# main.net
KiCad netlist of a schematic drawn in EAGLE
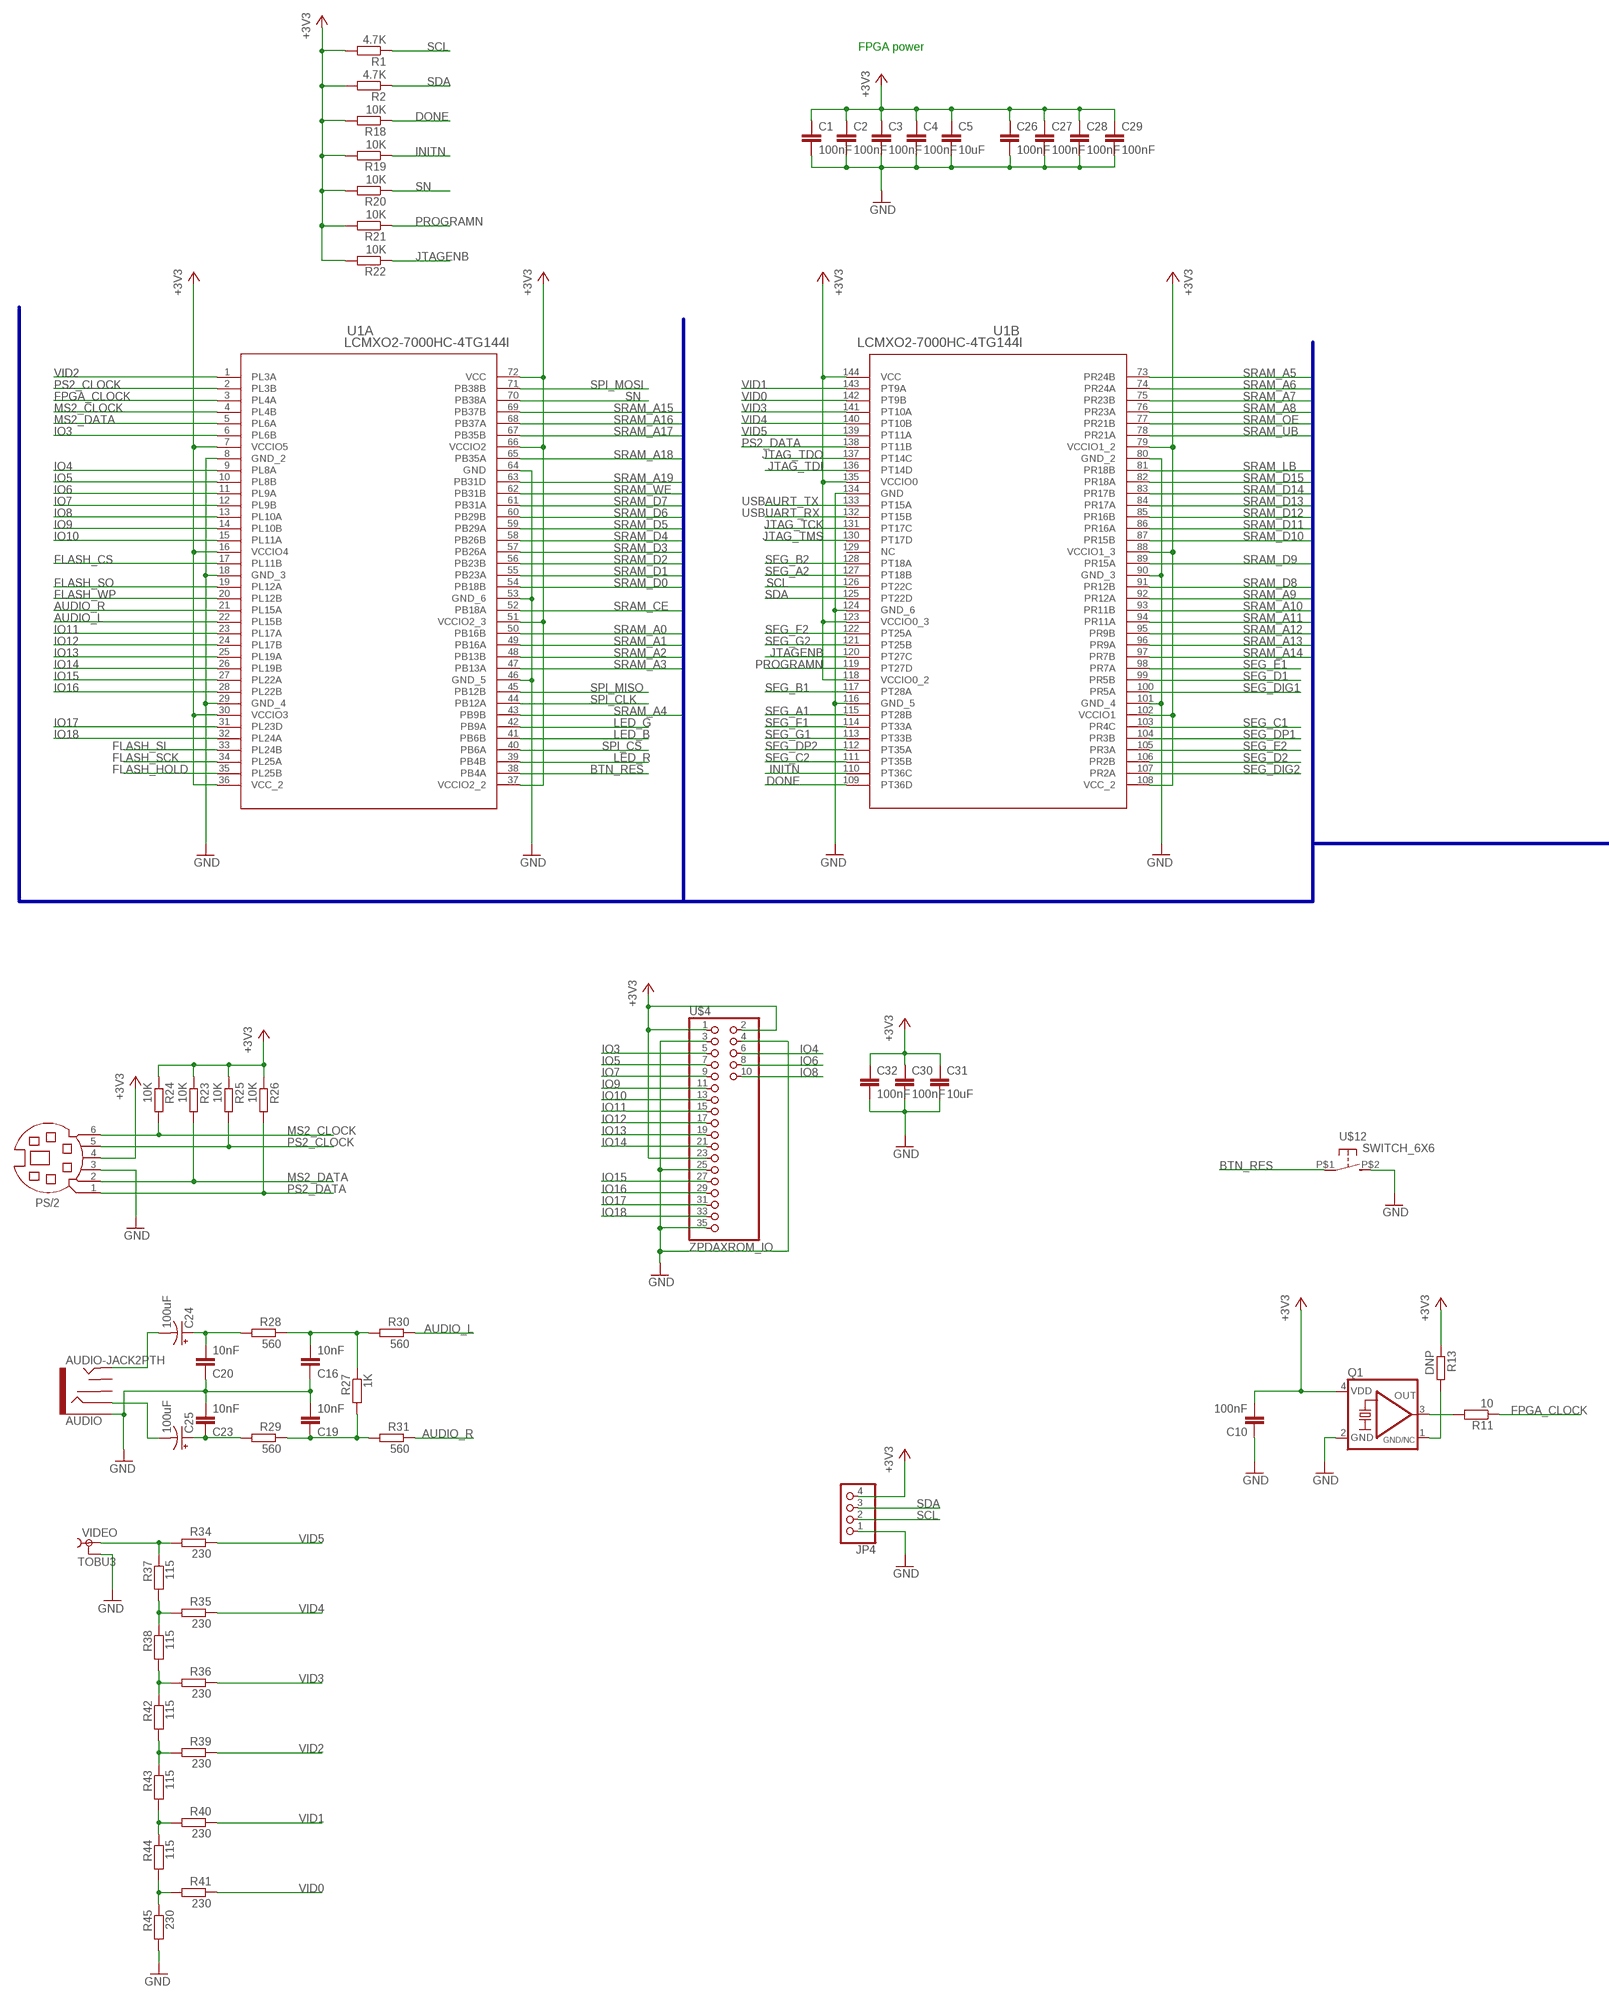
[diagram p0: schematic, sheet 1, part 1 of 2]
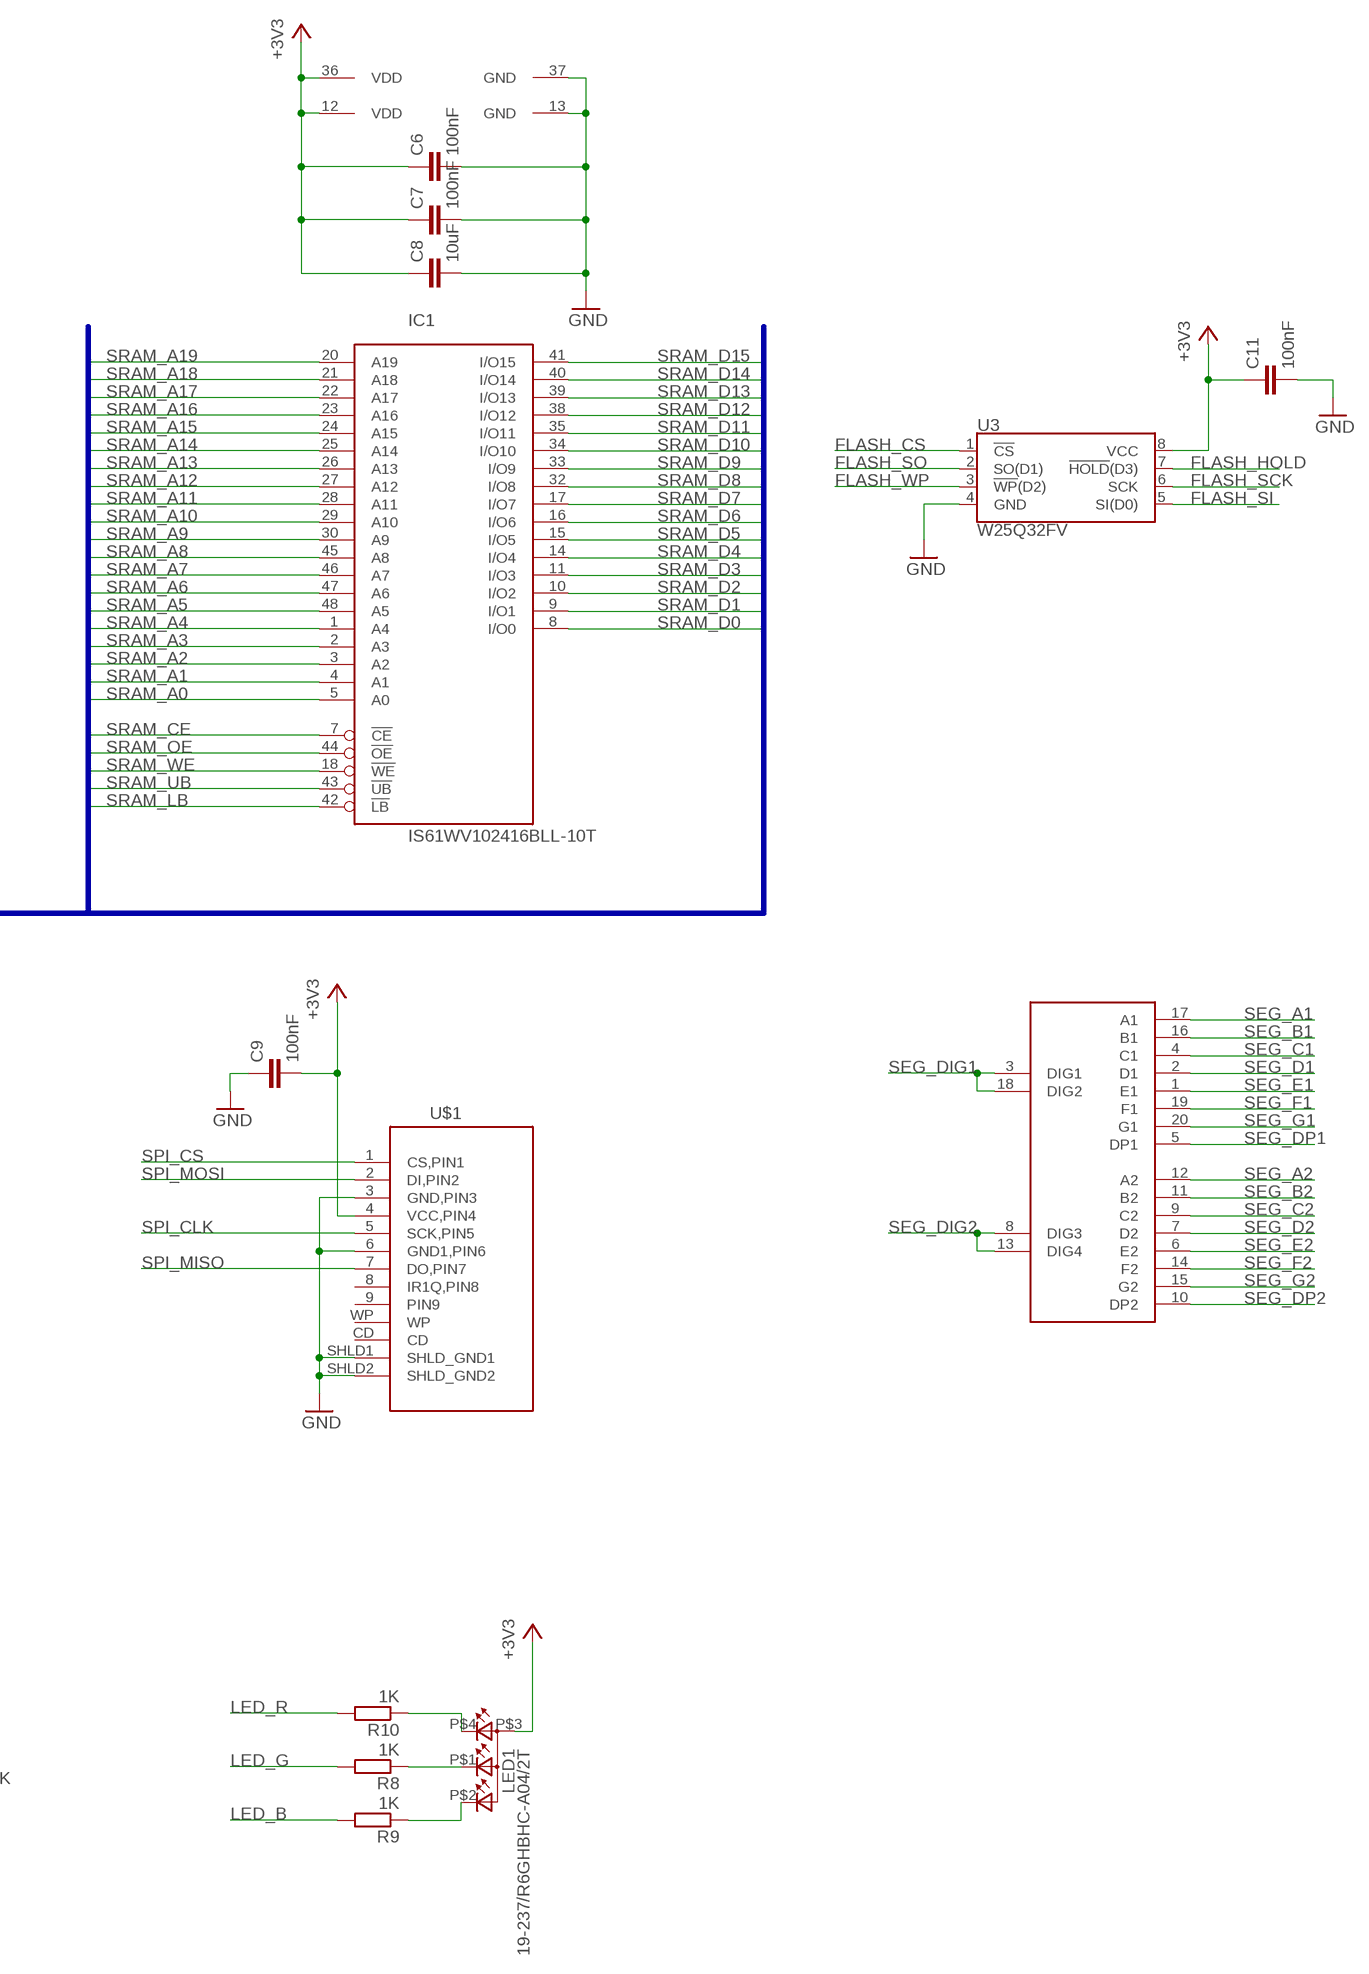
[diagram p1: schematic, sheet 1, part 2 of 2]
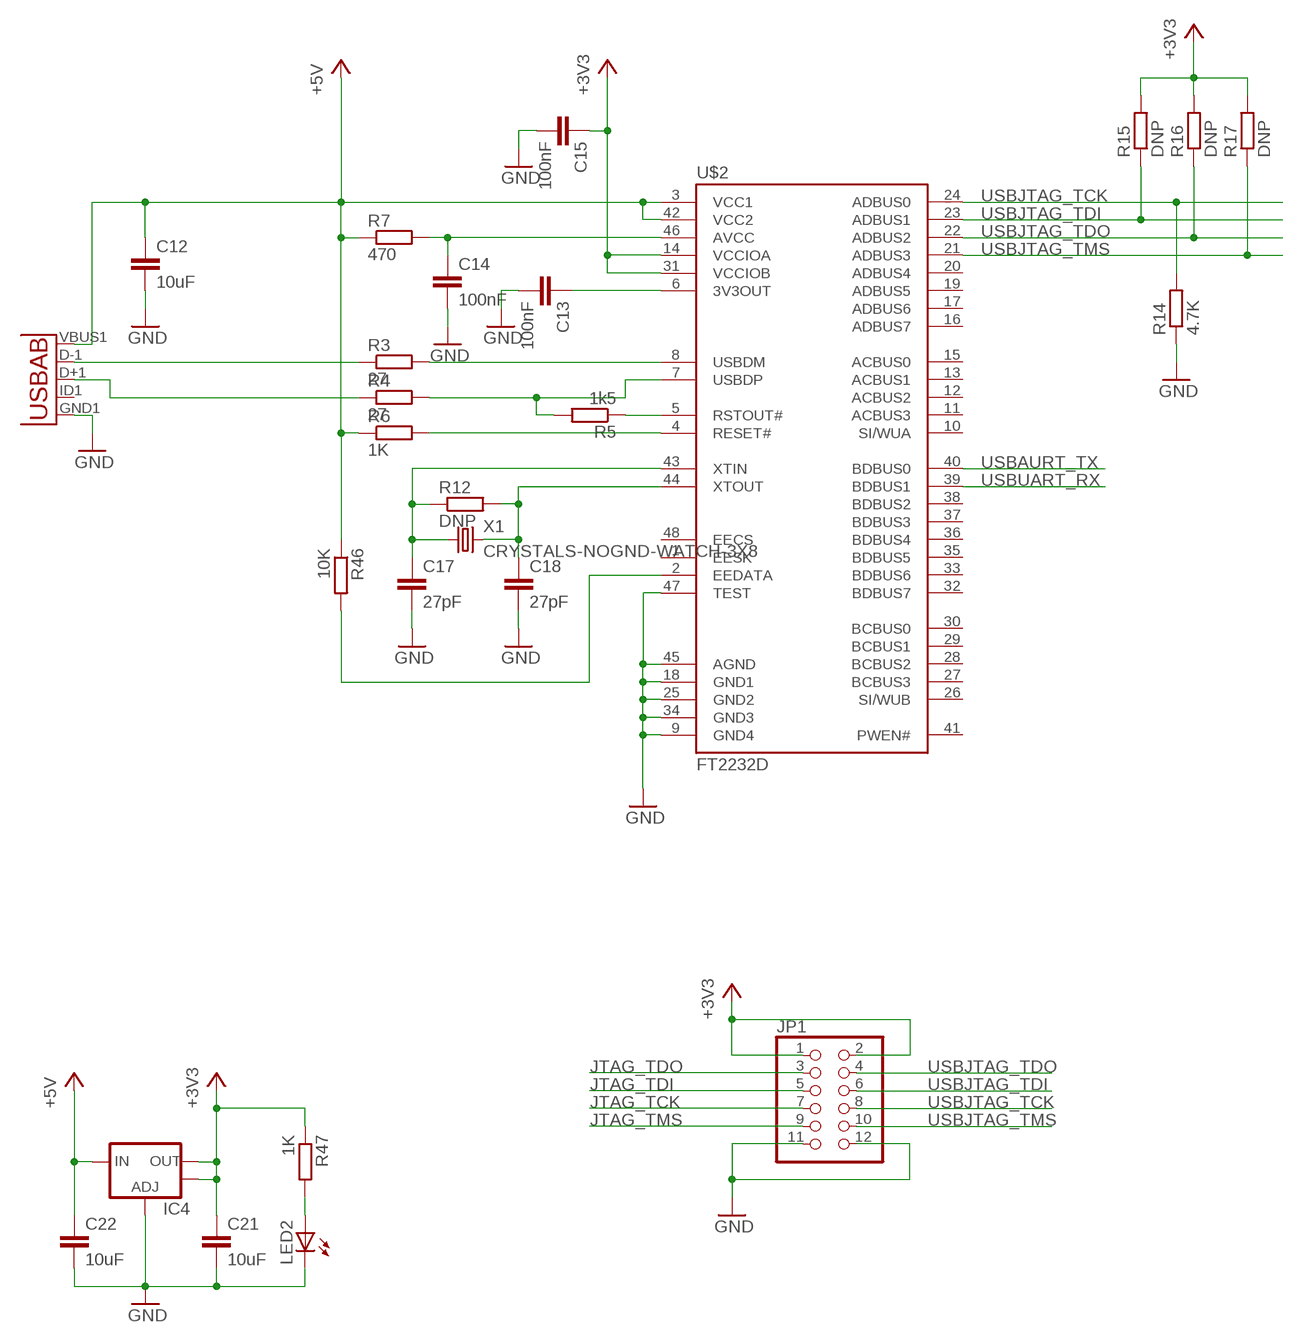
[diagram p2: schematic, sheet 2]

(export (version "E")
  (design (tool "Eeschema 10.0.6"))
  (components
    (comp (ref "AUDIO")
      (value "AUDIO-JACK2PTH")
      (footprint "eagle-import:AUDIO-JACK")
      (libsource (lib "eagle-import") (part "AUDIO-JACK2PTH"))
    )
    (comp (ref "C1")
      (value "100nF")
      (footprint "eagle-import:C0603")
      (libsource (lib "eagle-import") (part "C-EUC0603"))
    )
    (comp (ref "C2")
      (value "100nF")
      (footprint "eagle-import:C0603")
      (libsource (lib "eagle-import") (part "C-EUC0603"))
    )
    (comp (ref "C3")
      (value "100nF")
      (footprint "eagle-import:C0603")
      (libsource (lib "eagle-import") (part "C-EUC0603"))
    )
    (comp (ref "C4")
      (value "100nF")
      (footprint "eagle-import:C0603")
      (libsource (lib "eagle-import") (part "C-EUC0603"))
    )
    (comp (ref "C5")
      (value "10uF")
      (footprint "eagle-import:C0805")
      (libsource (lib "eagle-import") (part "C-EUC0805"))
    )
    (comp (ref "C6")
      (value "100nF")
      (footprint "eagle-import:C0603")
      (libsource (lib "eagle-import") (part "C-EUC0603"))
    )
    (comp (ref "C7")
      (value "100nF")
      (footprint "eagle-import:C0603")
      (libsource (lib "eagle-import") (part "C-EUC0603"))
    )
    (comp (ref "C8")
      (value "10uF")
      (footprint "eagle-import:C0805")
      (libsource (lib "eagle-import") (part "C-EUC0805"))
    )
    (comp (ref "C9")
      (value "100nF")
      (footprint "eagle-import:C0603")
      (libsource (lib "eagle-import") (part "C-EUC0603"))
    )
    (comp (ref "C10")
      (value "100nF")
      (footprint "eagle-import:C0603")
      (libsource (lib "eagle-import") (part "C-EUC0603"))
    )
    (comp (ref "C11")
      (value "100nF")
      (footprint "eagle-import:C0603")
      (libsource (lib "eagle-import") (part "C-EUC0603"))
    )
    (comp (ref "C16")
      (value "10nF")
      (footprint "eagle-import:C0603")
      (libsource (lib "eagle-import") (part "C-EUC0603"))
    )
    (comp (ref "C19")
      (value "10nF")
      (footprint "eagle-import:C0603")
      (libsource (lib "eagle-import") (part "C-EUC0603"))
    )
    (comp (ref "C20")
      (value "10nF")
      (footprint "eagle-import:C0603")
      (libsource (lib "eagle-import") (part "C-EUC0603"))
    )
    (comp (ref "C23")
      (value "10nF")
      (footprint "eagle-import:C0603")
      (libsource (lib "eagle-import") (part "C-EUC0603"))
    )
    (comp (ref "C24")
      (value "100uF")
      (footprint "eagle-import:EIA7343")
      (libsource (lib "eagle-import") (part "CAP_POL7343"))
    )
    (comp (ref "C25")
      (value "100uF")
      (footprint "eagle-import:EIA7343")
      (libsource (lib "eagle-import") (part "CAP_POL7343"))
    )
    (comp (ref "C26")
      (value "100nF")
      (footprint "eagle-import:C0603")
      (libsource (lib "eagle-import") (part "C-EUC0603"))
    )
    (comp (ref "C27")
      (value "100nF")
      (footprint "eagle-import:C0603")
      (libsource (lib "eagle-import") (part "C-EUC0603"))
    )
    (comp (ref "C28")
      (value "100nF")
      (footprint "eagle-import:C0603")
      (libsource (lib "eagle-import") (part "C-EUC0603"))
    )
    (comp (ref "C29")
      (value "100nF")
      (footprint "eagle-import:C0603")
      (libsource (lib "eagle-import") (part "C-EUC0603"))
    )
    (comp (ref "C30")
      (value "100nF")
      (footprint "eagle-import:C0603")
      (libsource (lib "eagle-import") (part "C-EUC0603"))
    )
    (comp (ref "C31")
      (value "10uF")
      (footprint "eagle-import:C0805")
      (libsource (lib "eagle-import") (part "C-EUC0805"))
    )
    (comp (ref "C32")
      (value "100nF")
      (footprint "eagle-import:C0603")
      (libsource (lib "eagle-import") (part "C-EUC0603"))
    )
    (comp (ref "IC1")
      (value "IS61WV102416BLL-10T")
      (footprint "eagle-import:TSOP-I-48-12X40MM")
      (libsource (lib "eagle-import") (part "IS61WV102416BLL-T10"))
    )
    (comp (ref "JP4")
      (value "PINHD-1X4")
      (footprint "eagle-import:1X04")
      (libsource (lib "eagle-import") (part "PINHD-1X4"))
    )
    (comp (ref "LED1")
      (value "19-237/R6GHBHC-A04/2T")
      (footprint "eagle-import:19-237_R6GHBHC-A04_2T")
      (libsource (lib "eagle-import") (part "19-237/R6GHBHC-A04/2T"))
    )
    (comp (ref "PS/2")
      (value "MD06SS")
      (footprint "eagle-import:MDIN06SS")
      (libsource (lib "eagle-import") (part "MD06SS"))
    )
    (comp (ref "Q1")
      (value "KXO-TCXO-CMOS-82")
      (footprint "eagle-import:7.0X5.0_KXO-82-TCXO")
      (libsource (lib "eagle-import") (part "KXO-TCXO-CMOS-82"))
    )
    (comp (ref "R1")
      (value "4.7K")
      (footprint "eagle-import:R0603")
      (libsource (lib "eagle-import") (part "R-EU_R0603"))
    )
    (comp (ref "R2")
      (value "4.7K")
      (footprint "eagle-import:R0603")
      (libsource (lib "eagle-import") (part "R-EU_R0603"))
    )
    (comp (ref "R8")
      (value "1K")
      (footprint "eagle-import:R0603")
      (libsource (lib "eagle-import") (part "R-EU_R0603"))
    )
    (comp (ref "R9")
      (value "1K")
      (footprint "eagle-import:R0603")
      (libsource (lib "eagle-import") (part "R-EU_R0603"))
    )
    (comp (ref "R10")
      (value "1K")
      (footprint "eagle-import:R0603")
      (libsource (lib "eagle-import") (part "R-EU_R0603"))
    )
    (comp (ref "R11")
      (value "10")
      (footprint "eagle-import:R0603")
      (libsource (lib "eagle-import") (part "R-EU_R0603"))
    )
    (comp (ref "R13")
      (value "DNP")
      (footprint "eagle-import:R0603")
      (libsource (lib "eagle-import") (part "R-EU_R0603"))
    )
    (comp (ref "R18")
      (value "10K")
      (footprint "eagle-import:R0603")
      (libsource (lib "eagle-import") (part "R-EU_R0603"))
    )
    (comp (ref "R19")
      (value "10K")
      (footprint "eagle-import:R0603")
      (libsource (lib "eagle-import") (part "R-EU_R0603"))
    )
    (comp (ref "R20")
      (value "10K")
      (footprint "eagle-import:R0603")
      (libsource (lib "eagle-import") (part "R-EU_R0603"))
    )
    (comp (ref "R21")
      (value "10K")
      (footprint "eagle-import:R0603")
      (libsource (lib "eagle-import") (part "R-EU_R0603"))
    )
    (comp (ref "R22")
      (value "10K")
      (footprint "eagle-import:R0603")
      (libsource (lib "eagle-import") (part "R-EU_R0603"))
    )
    (comp (ref "R23")
      (value "10K")
      (footprint "eagle-import:R0603")
      (libsource (lib "eagle-import") (part "R-EU_R0603"))
    )
    (comp (ref "R24")
      (value "10K")
      (footprint "eagle-import:R0603")
      (libsource (lib "eagle-import") (part "R-EU_R0603"))
    )
    (comp (ref "R25")
      (value "10K")
      (footprint "eagle-import:R0603")
      (libsource (lib "eagle-import") (part "R-EU_R0603"))
    )
    (comp (ref "R26")
      (value "10K")
      (footprint "eagle-import:R0603")
      (libsource (lib "eagle-import") (part "R-EU_R0603"))
    )
    (comp (ref "R27")
      (value "1K")
      (footprint "eagle-import:R0603")
      (libsource (lib "eagle-import") (part "R-EU_R0603"))
    )
    (comp (ref "R28")
      (value "560")
      (footprint "eagle-import:R0603")
      (libsource (lib "eagle-import") (part "R-EU_R0603"))
    )
    (comp (ref "R29")
      (value "560")
      (footprint "eagle-import:R0603")
      (libsource (lib "eagle-import") (part "R-EU_R0603"))
    )
    (comp (ref "R30")
      (value "560")
      (footprint "eagle-import:R0603")
      (libsource (lib "eagle-import") (part "R-EU_R0603"))
    )
    (comp (ref "R31")
      (value "560")
      (footprint "eagle-import:R0603")
      (libsource (lib "eagle-import") (part "R-EU_R0603"))
    )
    (comp (ref "R34")
      (value "230")
      (footprint "eagle-import:R0603")
      (libsource (lib "eagle-import") (part "R-EU_R0603"))
    )
    (comp (ref "R35")
      (value "230")
      (footprint "eagle-import:R0603")
      (libsource (lib "eagle-import") (part "R-EU_R0603"))
    )
    (comp (ref "R36")
      (value "230")
      (footprint "eagle-import:R0603")
      (libsource (lib "eagle-import") (part "R-EU_R0603"))
    )
    (comp (ref "R37")
      (value "115")
      (footprint "eagle-import:R0603")
      (libsource (lib "eagle-import") (part "R-EU_R0603"))
    )
    (comp (ref "R38")
      (value "115")
      (footprint "eagle-import:R0603")
      (libsource (lib "eagle-import") (part "R-EU_R0603"))
    )
    (comp (ref "R39")
      (value "230")
      (footprint "eagle-import:R0603")
      (libsource (lib "eagle-import") (part "R-EU_R0603"))
    )
    (comp (ref "R40")
      (value "230")
      (footprint "eagle-import:R0603")
      (libsource (lib "eagle-import") (part "R-EU_R0603"))
    )
    (comp (ref "R41")
      (value "230")
      (footprint "eagle-import:R0603")
      (libsource (lib "eagle-import") (part "R-EU_R0603"))
    )
    (comp (ref "R42")
      (value "115")
      (footprint "eagle-import:R0603")
      (libsource (lib "eagle-import") (part "R-EU_R0603"))
    )
    (comp (ref "R43")
      (value "115")
      (footprint "eagle-import:R0603")
      (libsource (lib "eagle-import") (part "R-EU_R0603"))
    )
    (comp (ref "R44")
      (value "115")
      (footprint "eagle-import:R0603")
      (libsource (lib "eagle-import") (part "R-EU_R0603"))
    )
    (comp (ref "R45")
      (value "230")
      (footprint "eagle-import:R0603")
      (libsource (lib "eagle-import") (part "R-EU_R0603"))
    )
    (comp (ref "U$1")
      (value "FCI_SD_SOCKET")
      (footprint "eagle-import:SD-MMC_SOCKET-PP")
      (fields (field (name "MF") "FCI") (field (name "MPN") "10067847-001RLF"))
      (libsource (lib "eagle-import") (part "FCI_SD_SOCKET"))
    )
    (comp (ref "U$3")
      (value "GS2020CR-G")
      (footprint "eagle-import:GS2020CR")
      (libsource (lib "eagle-import") (part "GS2020CR-G"))
    )
    (comp (ref "U$4")
      (value "ZPDAXROM_IO")
      (footprint "eagle-import:2X18_ZPDAXROM_IO")
      (libsource (lib "eagle-import") (part "ZPDAXROM_IO"))
    )
    (comp (ref "U$12")
      (value "SWITCH_6X6")
      (footprint "eagle-import:SWITCH_6X6")
      (libsource (lib "eagle-import") (part "SWITCH_6X6"))
    )
    (comp (ref "U1")
      (value "LCMXO2-7000HC-4TG144I")
      (footprint "eagle-import:TQFP144")
      (fields (field (name "MANUFACTURER_PART_NUMBER") "LCMXO27000HC4TG144I"))
      (libsource (lib "eagle-import") (part "LCMXO2-7000HC-4TG144I"))
    )
    (comp (ref "U3")
      (value "W25Q32FV")
      (footprint "eagle-import:SOIC-8")
      (libsource (lib "eagle-import") (part "W25Q32FVSS"))
    )
    (comp (ref "VIDEO")
      (value "TOBU3")
      (footprint "eagle-import:TOBU3")
      (fields (field (name "MF") "FARNELL") (field (name "MPN") "TOBU 3"))
      (libsource (lib "eagle-import") (part "TOBU3"))
    )
    (comp (ref "C12")
      (value "10uF")
      (footprint "eagle-import:C0805")
      (libsource (lib "eagle-import") (part "C-EUC0805"))
    )
    (comp (ref "C13")
      (value "100nF")
      (footprint "eagle-import:C0603")
      (libsource (lib "eagle-import") (part "C-EUC0603"))
    )
    (comp (ref "C14")
      (value "100nF")
      (footprint "eagle-import:C0603")
      (libsource (lib "eagle-import") (part "C-EUC0603"))
    )
    (comp (ref "C15")
      (value "100nF")
      (footprint "eagle-import:C0603")
      (libsource (lib "eagle-import") (part "C-EUC0603"))
    )
    (comp (ref "C17")
      (value "27pF")
      (footprint "eagle-import:C0603")
      (libsource (lib "eagle-import") (part "C-EUC0603"))
    )
    (comp (ref "C18")
      (value "27pF")
      (footprint "eagle-import:C0603")
      (libsource (lib "eagle-import") (part "C-EUC0603"))
    )
    (comp (ref "C21")
      (value "10uF")
      (footprint "eagle-import:C0805")
      (libsource (lib "eagle-import") (part "C-EUC0805"))
    )
    (comp (ref "C22")
      (value "10uF")
      (footprint "eagle-import:C0805")
      (libsource (lib "eagle-import") (part "C-EUC0805"))
    )
    (comp (ref "IC4")
      (value "V_REG_LM1117SOT223")
      (footprint "eagle-import:SOT223")
      (libsource (lib "eagle-import") (part "V_REG_LM1117SOT223"))
    )
    (comp (ref "JP1")
      (value "PINHD-2X6")
      (footprint "eagle-import:2X06")
      (libsource (lib "eagle-import") (part "PINHD-2X6"))
    )
    (comp (ref "LED2")
      (value "LEDCHIPLED_0603")
      (footprint "eagle-import:CHIPLED_0603")
      (libsource (lib "eagle-import") (part "LEDCHIPLED_0603"))
    )
    (comp (ref "R3")
      (value "27")
      (footprint "eagle-import:R0603")
      (libsource (lib "eagle-import") (part "R-EU_R0603"))
    )
    (comp (ref "R4")
      (value "27")
      (footprint "eagle-import:R0603")
      (libsource (lib "eagle-import") (part "R-EU_R0603"))
    )
    (comp (ref "R5")
      (value "1k5")
      (footprint "eagle-import:R0603")
      (libsource (lib "eagle-import") (part "R-EU_R0603"))
    )
    (comp (ref "R6")
      (value "1K")
      (footprint "eagle-import:R0603")
      (libsource (lib "eagle-import") (part "R-EU_R0603"))
    )
    (comp (ref "R7")
      (value "470")
      (footprint "eagle-import:R0603")
      (libsource (lib "eagle-import") (part "R-EU_R0603"))
    )
    (comp (ref "R12")
      (value "DNP")
      (footprint "eagle-import:R0603")
      (libsource (lib "eagle-import") (part "R-EU_R0603"))
    )
    (comp (ref "R14")
      (value "4.7K")
      (footprint "eagle-import:R0603")
      (libsource (lib "eagle-import") (part "R-EU_R0603"))
    )
    (comp (ref "R15")
      (value "DNP")
      (footprint "eagle-import:R0603")
      (libsource (lib "eagle-import") (part "R-EU_R0603"))
    )
    (comp (ref "R16")
      (value "DNP")
      (footprint "eagle-import:R0603")
      (libsource (lib "eagle-import") (part "R-EU_R0603"))
    )
    (comp (ref "R17")
      (value "DNP")
      (footprint "eagle-import:R0603")
      (libsource (lib "eagle-import") (part "R-EU_R0603"))
    )
    (comp (ref "R46")
      (value "10K")
      (footprint "eagle-import:R0603")
      (libsource (lib "eagle-import") (part "R-EU_R0603"))
    )
    (comp (ref "R47")
      (value "1K")
      (footprint "eagle-import:R0603")
      (libsource (lib "eagle-import") (part "R-EU_R0603"))
    )
    (comp (ref "U$2")
      (value "FT2232D")
      (footprint "eagle-import:LQFP-48")
      (libsource (lib "eagle-import") (part "FT2232D"))
    )
    (comp (ref "U2")
      (value "USB\"\"")
      (footprint "eagle-import:USB-MICRO-SMD")
      (libsource (lib "eagle-import") (part "USB{dblquote}{dblquote}"))
    )
    (comp (ref "X1")
      (value "CRYSTALS-NOGND-WATCH-3X8")
      (footprint "eagle-import:WATCH-3X8")
      (libsource (lib "eagle-import") (part "CRYSTALS-NOGND-WATCH-3X8"))
    )
  )
  (nets
    (net (code "1") (name "+3V3") (class "Default")
      (node (ref "C1") (pin "1") (pinfunction "1_1") (pintype "passive"))
      (node (ref "C10") (pin "2") (pinfunction "2_2") (pintype "passive"))
      (node (ref "C11") (pin "1") (pinfunction "1_1") (pintype "passive"))
      (node (ref "C15") (pin "1") (pinfunction "1_1") (pintype "passive"))
      (node (ref "C2") (pin "1") (pinfunction "1_1") (pintype "passive"))
      (node (ref "C21") (pin "1") (pinfunction "1_1") (pintype "passive"))
      (node (ref "C26") (pin "1") (pinfunction "1_1") (pintype "passive"))
      (node (ref "C27") (pin "1") (pinfunction "1_1") (pintype "passive"))
      (node (ref "C28") (pin "1") (pinfunction "1_1") (pintype "passive"))
      (node (ref "C29") (pin "1") (pinfunction "1_1") (pintype "passive"))
      (node (ref "C3") (pin "1") (pinfunction "1_1") (pintype "passive"))
      (node (ref "C30") (pin "1") (pinfunction "1_1") (pintype "passive"))
      (node (ref "C31") (pin "1") (pinfunction "1_1") (pintype "passive"))
      (node (ref "C32") (pin "1") (pinfunction "1_1") (pintype "passive"))
      (node (ref "C4") (pin "1") (pinfunction "1_1") (pintype "passive"))
      (node (ref "C5") (pin "1") (pinfunction "1_1") (pintype "passive"))
      (node (ref "C6") (pin "1") (pinfunction "1_1") (pintype "passive"))
      (node (ref "C7") (pin "1") (pinfunction "1_1") (pintype "passive"))
      (node (ref "C8") (pin "1") (pinfunction "1_1") (pintype "passive"))
      (node (ref "C9") (pin "2") (pinfunction "2_2") (pintype "passive"))
      (node (ref "IC1") (pin "12") (pinfunction "VDD_12") (pintype "power_in"))
      (node (ref "IC1") (pin "36") (pinfunction "VDD_36") (pintype "power_in"))
      (node (ref "IC4") (pin "2") (pinfunction "OUT_2") (pintype "output"))
      (node (ref "IC4") (pin "4") (pinfunction "OUT_4") (pintype "output"))
      (node (ref "JP1") (pin "1") (pinfunction "1_1") (pintype "passive"))
      (node (ref "JP1") (pin "2") (pinfunction "2_2") (pintype "passive"))
      (node (ref "JP4") (pin "4") (pinfunction "4_4") (pintype "passive"))
      (node (ref "LED1") (pin "P$3") (pinfunction "A_P$3") (pintype "passive"))
      (node (ref "PS/2") (pin "4") (pinfunction "4_4") (pintype "passive"))
      (node (ref "Q1") (pin "4") (pinfunction "VDD_4") (pintype "power_in"))
      (node (ref "R1") (pin "2") (pinfunction "2_2") (pintype "passive"))
      (node (ref "R13") (pin "1") (pinfunction "1_1") (pintype "passive"))
      (node (ref "R15") (pin "2") (pinfunction "2_2") (pintype "passive"))
      (node (ref "R16") (pin "2") (pinfunction "2_2") (pintype "passive"))
      (node (ref "R17") (pin "2") (pinfunction "2_2") (pintype "passive"))
      (node (ref "R18") (pin "2") (pinfunction "2_2") (pintype "passive"))
      (node (ref "R19") (pin "2") (pinfunction "2_2") (pintype "passive"))
      (node (ref "R2") (pin "2") (pinfunction "2_2") (pintype "passive"))
      (node (ref "R20") (pin "2") (pinfunction "2_2") (pintype "passive"))
      (node (ref "R21") (pin "2") (pinfunction "2_2") (pintype "passive"))
      (node (ref "R22") (pin "2") (pinfunction "2_2") (pintype "passive"))
      (node (ref "R23") (pin "1") (pinfunction "1_1") (pintype "passive"))
      (node (ref "R24") (pin "1") (pinfunction "1_1") (pintype "passive"))
      (node (ref "R25") (pin "1") (pinfunction "1_1") (pintype "passive"))
      (node (ref "R26") (pin "1") (pinfunction "1_1") (pintype "passive"))
      (node (ref "R47") (pin "1") (pinfunction "1_1") (pintype "passive"))
      (node (ref "U$1") (pin "4") (pinfunction "VCC,PIN4_4") (pintype "bidirectional"))
      (node (ref "U$2") (pin "14") (pinfunction "VCCIOA_14") (pintype "power_in"))
      (node (ref "U$2") (pin "31") (pinfunction "VCCIOB_31") (pintype "bidirectional"))
      (node (ref "U$4") (pin "1") (pinfunction "1_1") (pintype "passive"))
      (node (ref "U$4") (pin "2") (pinfunction "2_2") (pintype "passive"))
      (node (ref "U$4") (pin "23") (pinfunction "23_23") (pintype "passive"))
      (node (ref "U1") (pin "102") (pinfunction "VCCIO1_102") (pintype "power_in"))
      (node (ref "U1") (pin "108") (pinfunction "VCC_2_108") (pintype "power_in"))
      (node (ref "U1") (pin "118") (pinfunction "VCCIO0_2_118") (pintype "power_in"))
      (node (ref "U1") (pin "123") (pinfunction "VCCIO0_3_123") (pintype "power_in"))
      (node (ref "U1") (pin "135") (pinfunction "VCCIO0_135") (pintype "power_in"))
      (node (ref "U1") (pin "144") (pinfunction "VCC_144") (pintype "power_in"))
      (node (ref "U1") (pin "16") (pinfunction "VCCIO4_16") (pintype "power_in"))
      (node (ref "U1") (pin "30") (pinfunction "VCCIO3_30") (pintype "power_in"))
      (node (ref "U1") (pin "36") (pinfunction "VCC_2_36") (pintype "power_in"))
      (node (ref "U1") (pin "37") (pinfunction "VCCIO2_2_37") (pintype "power_in"))
      (node (ref "U1") (pin "51") (pinfunction "VCCIO2_3_51") (pintype "power_in"))
      (node (ref "U1") (pin "66") (pinfunction "VCCIO2_66") (pintype "power_in"))
      (node (ref "U1") (pin "7") (pinfunction "VCCIO5_7") (pintype "power_in"))
      (node (ref "U1") (pin "72") (pinfunction "VCC_72") (pintype "power_in"))
      (node (ref "U1") (pin "79") (pinfunction "VCCIO1_2_79") (pintype "power_in"))
      (node (ref "U1") (pin "88") (pinfunction "VCCIO1_3_88") (pintype "power_in"))
      (node (ref "U3") (pin "8") (pinfunction "VCC_8") (pintype "bidirectional"))
    )
    (net (code "2") (name "+5V") (class "Default")
      (node (ref "C12") (pin "1") (pinfunction "1_1") (pintype "passive"))
      (node (ref "C22") (pin "1") (pinfunction "1_1") (pintype "passive"))
      (node (ref "IC4") (pin "3") (pinfunction "IN_3") (pintype "input"))
      (node (ref "R46") (pin "1") (pinfunction "1_1") (pintype "passive"))
      (node (ref "R6") (pin "1") (pinfunction "1_1") (pintype "passive"))
      (node (ref "R7") (pin "1") (pinfunction "1_1") (pintype "passive"))
      (node (ref "U$2") (pin "3") (pinfunction "VCC1_3") (pintype "power_in"))
      (node (ref "U$2") (pin "42") (pinfunction "VCC2_42") (pintype "power_in"))
      (node (ref "U2") (pin "VBUS1") (pinfunction "VBUS_VBUS1") (pintype "bidirectional"))
    )
    (net (code "3") (name "AUDIO_L") (class "Default")
      (node (ref "R30") (pin "1") (pinfunction "1_1") (pintype "passive"))
      (node (ref "U1") (pin "22") (pinfunction "PL15B_22") (pintype "passive"))
    )
    (net (code "4") (name "AUDIO_R") (class "Default")
      (node (ref "R31") (pin "1") (pinfunction "1_1") (pintype "passive"))
      (node (ref "U1") (pin "21") (pinfunction "PL15A_21") (pintype "passive"))
    )
    (net (code "5") (name "BTN_RES") (class "Default")
      (node (ref "U$12") (pin "P$1") (pinfunction "P_P$1") (pintype "passive"))
      (node (ref "U1") (pin "38") (pinfunction "PB4A_38") (pintype "passive"))
    )
    (net (code "6") (name "DONE") (class "Default")
      (node (ref "R18") (pin "1") (pinfunction "1_1") (pintype "passive"))
      (node (ref "U1") (pin "109") (pinfunction "PT36D_109") (pintype "passive"))
    )
    (net (code "7") (name "FLASH_CS") (class "Default")
      (node (ref "U1") (pin "17") (pinfunction "PL11B_17") (pintype "passive"))
      (node (ref "U3") (pin "1") (pinfunction "~{CS}_1") (pintype "bidirectional"))
    )
    (net (code "8") (name "FLASH_HOLD") (class "Default")
      (node (ref "U1") (pin "35") (pinfunction "PL25B_35") (pintype "passive"))
      (node (ref "U3") (pin "7") (pinfunction "~{HOLD}(D3)_7") (pintype "bidirectional"))
    )
    (net (code "9") (name "FLASH_SCK") (class "Default")
      (node (ref "U1") (pin "34") (pinfunction "PL25A_34") (pintype "passive"))
      (node (ref "U3") (pin "6") (pinfunction "SCK_6") (pintype "bidirectional"))
    )
    (net (code "10") (name "FLASH_SI") (class "Default")
      (node (ref "U1") (pin "33") (pinfunction "PL24B_33") (pintype "passive"))
      (node (ref "U3") (pin "5") (pinfunction "SI(D0)_5") (pintype "bidirectional"))
    )
    (net (code "11") (name "FLASH_SO") (class "Default")
      (node (ref "U1") (pin "19") (pinfunction "PL12A_19") (pintype "passive"))
      (node (ref "U3") (pin "2") (pinfunction "SO(D1)_2") (pintype "bidirectional"))
    )
    (net (code "12") (name "FLASH_WP") (class "Default")
      (node (ref "U1") (pin "20") (pinfunction "PL12B_20") (pintype "passive"))
      (node (ref "U3") (pin "3") (pinfunction "~{WP}(D2)_3") (pintype "bidirectional"))
    )
    (net (code "13") (name "FPGA_CLOCK") (class "Default")
      (node (ref "R11") (pin "1") (pinfunction "1_1") (pintype "passive"))
      (node (ref "U1") (pin "3") (pinfunction "PL4A_3") (pintype "passive"))
    )
    (net (code "14") (name "GND") (class "Default")
      (node (ref "AUDIO") (pin "SLEEVE") (pinfunction "SLEEVE_SLEEVE") (pintype "bidirectional"))
      (node (ref "C1") (pin "2") (pinfunction "2_2") (pintype "passive"))
      (node (ref "C10") (pin "1") (pinfunction "1_1") (pintype "passive"))
      (node (ref "C11") (pin "2") (pinfunction "2_2") (pintype "passive"))
      (node (ref "C12") (pin "2") (pinfunction "2_2") (pintype "passive"))
      (node (ref "C13") (pin "2") (pinfunction "2_2") (pintype "passive"))
      (node (ref "C14") (pin "2") (pinfunction "2_2") (pintype "passive"))
      (node (ref "C15") (pin "2") (pinfunction "2_2") (pintype "passive"))
      (node (ref "C16") (pin "1") (pinfunction "1_1") (pintype "passive"))
      (node (ref "C17") (pin "2") (pinfunction "2_2") (pintype "passive"))
      (node (ref "C18") (pin "2") (pinfunction "2_2") (pintype "passive"))
      (node (ref "C19") (pin "2") (pinfunction "2_2") (pintype "passive"))
      (node (ref "C2") (pin "2") (pinfunction "2_2") (pintype "passive"))
      (node (ref "C20") (pin "1") (pinfunction "1_1") (pintype "passive"))
      (node (ref "C21") (pin "2") (pinfunction "2_2") (pintype "passive"))
      (node (ref "C22") (pin "2") (pinfunction "2_2") (pintype "passive"))
      (node (ref "C23") (pin "2") (pinfunction "2_2") (pintype "passive"))
      (node (ref "C26") (pin "2") (pinfunction "2_2") (pintype "passive"))
      (node (ref "C27") (pin "2") (pinfunction "2_2") (pintype "passive"))
      (node (ref "C28") (pin "2") (pinfunction "2_2") (pintype "passive"))
      (node (ref "C29") (pin "2") (pinfunction "2_2") (pintype "passive"))
      (node (ref "C3") (pin "2") (pinfunction "2_2") (pintype "passive"))
      (node (ref "C30") (pin "2") (pinfunction "2_2") (pintype "passive"))
      (node (ref "C31") (pin "2") (pinfunction "2_2") (pintype "passive"))
      (node (ref "C32") (pin "2") (pinfunction "2_2") (pintype "passive"))
      (node (ref "C4") (pin "2") (pinfunction "2_2") (pintype "passive"))
      (node (ref "C5") (pin "2") (pinfunction "2_2") (pintype "passive"))
      (node (ref "C6") (pin "2") (pinfunction "2_2") (pintype "passive"))
      (node (ref "C7") (pin "2") (pinfunction "2_2") (pintype "passive"))
      (node (ref "C8") (pin "2") (pinfunction "2_2") (pintype "passive"))
      (node (ref "C9") (pin "1") (pinfunction "1_1") (pintype "passive"))
      (node (ref "IC1") (pin "13") (pinfunction "GND_13") (pintype "power_in"))
      (node (ref "IC1") (pin "37") (pinfunction "GND_37") (pintype "power_in"))
      (node (ref "IC4") (pin "1") (pinfunction "ADJ_1") (pintype "input"))
      (node (ref "JP1") (pin "11") (pinfunction "11_11") (pintype "passive"))
      (node (ref "JP1") (pin "12") (pinfunction "12_12") (pintype "passive"))
      (node (ref "JP4") (pin "1") (pinfunction "1_1") (pintype "passive"))
      (node (ref "LED2") (pin "C") (pinfunction "C_C") (pintype "passive"))
      (node (ref "PS/2") (pin "3") (pinfunction "3_3") (pintype "passive"))
      (node (ref "Q1") (pin "2") (pinfunction "GND_2") (pintype "power_in"))
      (node (ref "R14") (pin "1") (pinfunction "1_1") (pintype "passive"))
      (node (ref "R45") (pin "2") (pinfunction "2_2") (pintype "passive"))
      (node (ref "U$1") (pin "3") (pinfunction "GND,PIN3_3") (pintype "bidirectional"))
      (node (ref "U$1") (pin "6") (pinfunction "GND1,PIN6_6") (pintype "bidirectional"))
      (node (ref "U$1") (pin "SHLD1") (pinfunction "SHLD_GND1_SHLD1") (pintype "bidirectional"))
      (node (ref "U$1") (pin "SHLD2") (pinfunction "SHLD_GND2_SHLD2") (pintype "bidirectional"))
      (node (ref "U$12") (pin "P$2") (pinfunction "S_P$2") (pintype "passive"))
      (node (ref "U$2") (pin "18") (pinfunction "GND1_18") (pintype "power_in"))
      (node (ref "U$2") (pin "25") (pinfunction "GND2_25") (pintype "power_in"))
      (node (ref "U$2") (pin "34") (pinfunction "GND3_34") (pintype "power_in"))
      (node (ref "U$2") (pin "45") (pinfunction "AGND_45") (pintype "power_in"))
      (node (ref "U$2") (pin "47") (pinfunction "TEST_47") (pintype "input"))
      (node (ref "U$2") (pin "9") (pinfunction "GND4_9") (pintype "bidirectional"))
      (node (ref "U$4") (pin "25") (pinfunction "25_25") (pintype "passive"))
      (node (ref "U$4") (pin "3") (pinfunction "3_3") (pintype "passive"))
      (node (ref "U$4") (pin "35") (pinfunction "35_35") (pintype "passive"))
      (node (ref "U$4") (pin "4") (pinfunction "4_4") (pintype "passive"))
      (node (ref "U1") (pin "101") (pinfunction "GND_4_101") (pintype "power_in"))
      (node (ref "U1") (pin "116") (pinfunction "GND_5_116") (pintype "power_in"))
      (node (ref "U1") (pin "124") (pinfunction "GND_6_124") (pintype "power_in"))
      (node (ref "U1") (pin "134") (pinfunction "GND_134") (pintype "power_in"))
      (node (ref "U1") (pin "18") (pinfunction "GND_3_18") (pintype "power_in"))
      (node (ref "U1") (pin "29") (pinfunction "GND_4_29") (pintype "power_in"))
      (node (ref "U1") (pin "46") (pinfunction "GND_5_46") (pintype "power_in"))
      (node (ref "U1") (pin "53") (pinfunction "GND_6_53") (pintype "power_in"))
      (node (ref "U1") (pin "64") (pinfunction "GND_64") (pintype "power_in"))
      (node (ref "U1") (pin "8") (pinfunction "GND_2_8") (pintype "power_in"))
      (node (ref "U1") (pin "80") (pinfunction "GND_2_80") (pintype "power_in"))
      (node (ref "U1") (pin "90") (pinfunction "GND_3_90") (pintype "power_in"))
      (node (ref "U2") (pin "GND1") (pinfunction "GND_GND1") (pintype "bidirectional"))
      (node (ref "U3") (pin "4") (pinfunction "GND_4") (pintype "bidirectional"))
      (node (ref "VIDEO") (pin "2") (pinfunction "2_2") (pintype "passive"))
      (node (ref "VIDEO") (pin "2@1") (pinfunction "2_2@1") (pintype "passive"))
      (node (ref "VIDEO") (pin "2@2") (pinfunction "2_2@2") (pintype "passive"))
    )
    (net (code "15") (name "INITN") (class "Default")
      (node (ref "R19") (pin "1") (pinfunction "1_1") (pintype "passive"))
      (node (ref "U1") (pin "110") (pinfunction "PT36C_110") (pintype "passive"))
    )
    (net (code "16") (name "IO3") (class "Default")
      (node (ref "U$4") (pin "5") (pinfunction "5_5") (pintype "passive"))
      (node (ref "U1") (pin "6") (pinfunction "PL6B_6") (pintype "passive"))
    )
    (net (code "17") (name "IO4") (class "Default")
      (node (ref "U$4") (pin "6") (pinfunction "6_6") (pintype "passive"))
      (node (ref "U1") (pin "9") (pinfunction "PL8A_9") (pintype "passive"))
    )
    (net (code "18") (name "IO5") (class "Default")
      (node (ref "U$4") (pin "7") (pinfunction "7_7") (pintype "passive"))
      (node (ref "U1") (pin "10") (pinfunction "PL8B_10") (pintype "passive"))
    )
    (net (code "19") (name "IO6") (class "Default")
      (node (ref "U$4") (pin "8") (pinfunction "8_8") (pintype "passive"))
      (node (ref "U1") (pin "11") (pinfunction "PL9A_11") (pintype "passive"))
    )
    (net (code "20") (name "IO7") (class "Default")
      (node (ref "U$4") (pin "9") (pinfunction "9_9") (pintype "passive"))
      (node (ref "U1") (pin "12") (pinfunction "PL9B_12") (pintype "passive"))
    )
    (net (code "21") (name "IO8") (class "Default")
      (node (ref "U$4") (pin "10") (pinfunction "10_10") (pintype "passive"))
      (node (ref "U1") (pin "13") (pinfunction "PL10A_13") (pintype "passive"))
    )
    (net (code "22") (name "IO9") (class "Default")
      (node (ref "U$4") (pin "11") (pinfunction "11_11") (pintype "passive"))
      (node (ref "U1") (pin "14") (pinfunction "PL10B_14") (pintype "passive"))
    )
    (net (code "23") (name "IO10") (class "Default")
      (node (ref "U$4") (pin "13") (pinfunction "13_13") (pintype "passive"))
      (node (ref "U1") (pin "15") (pinfunction "PL11A_15") (pintype "passive"))
    )
    (net (code "24") (name "IO11") (class "Default")
      (node (ref "U$4") (pin "15") (pinfunction "15_15") (pintype "passive"))
      (node (ref "U1") (pin "23") (pinfunction "PL17A_23") (pintype "passive"))
    )
    (net (code "25") (name "IO12") (class "Default")
      (node (ref "U$4") (pin "17") (pinfunction "17_17") (pintype "passive"))
      (node (ref "U1") (pin "24") (pinfunction "PL17B_24") (pintype "passive"))
    )
    (net (code "26") (name "IO13") (class "Default")
      (node (ref "U$4") (pin "19") (pinfunction "19_19") (pintype "passive"))
      (node (ref "U1") (pin "25") (pinfunction "PL19A_25") (pintype "passive"))
    )
    (net (code "27") (name "IO14") (class "Default")
      (node (ref "U$4") (pin "21") (pinfunction "21_21") (pintype "passive"))
      (node (ref "U1") (pin "26") (pinfunction "PL19B_26") (pintype "passive"))
    )
    (net (code "28") (name "IO15") (class "Default")
      (node (ref "U$4") (pin "27") (pinfunction "27_27") (pintype "passive"))
      (node (ref "U1") (pin "27") (pinfunction "PL22A_27") (pintype "passive"))
    )
    (net (code "29") (name "IO16") (class "Default")
      (node (ref "U$4") (pin "29") (pinfunction "29_29") (pintype "passive"))
      (node (ref "U1") (pin "28") (pinfunction "PL22B_28") (pintype "passive"))
    )
    (net (code "30") (name "IO17") (class "Default")
      (node (ref "U$4") (pin "31") (pinfunction "31_31") (pintype "passive"))
      (node (ref "U1") (pin "31") (pinfunction "PL23D_31") (pintype "passive"))
    )
    (net (code "31") (name "IO18") (class "Default")
      (node (ref "U$4") (pin "33") (pinfunction "33_33") (pintype "passive"))
      (node (ref "U1") (pin "32") (pinfunction "PL24A_32") (pintype "passive"))
    )
    (net (code "32") (name "JTAGENB") (class "Default")
      (node (ref "R22") (pin "1") (pinfunction "1_1") (pintype "passive"))
      (node (ref "U1") (pin "120") (pinfunction "PT27C_120") (pintype "passive"))
    )
    (net (code "33") (name "JTAG_TCK") (class "Default")
      (node (ref "JP1") (pin "7") (pinfunction "7_7") (pintype "passive"))
      (node (ref "U1") (pin "131") (pinfunction "PT17C_131") (pintype "passive"))
    )
    (net (code "34") (name "JTAG_TDI") (class "Default")
      (node (ref "JP1") (pin "5") (pinfunction "5_5") (pintype "passive"))
      (node (ref "U1") (pin "136") (pinfunction "PT14D_136") (pintype "passive"))
    )
    (net (code "35") (name "JTAG_TDO") (class "Default")
      (node (ref "JP1") (pin "3") (pinfunction "3_3") (pintype "passive"))
      (node (ref "U1") (pin "137") (pinfunction "PT14C_137") (pintype "passive"))
    )
    (net (code "36") (name "JTAG_TMS") (class "Default")
      (node (ref "JP1") (pin "9") (pinfunction "9_9") (pintype "passive"))
      (node (ref "U1") (pin "130") (pinfunction "PT17D_130") (pintype "passive"))
    )
    (net (code "37") (name "LED_B") (class "Default")
      (node (ref "R9") (pin "2") (pinfunction "2_2") (pintype "passive"))
      (node (ref "U1") (pin "41") (pinfunction "PB6B_41") (pintype "passive"))
    )
    (net (code "38") (name "LED_G") (class "Default")
      (node (ref "R8") (pin "2") (pinfunction "2_2") (pintype "passive"))
      (node (ref "U1") (pin "42") (pinfunction "PB9A_42") (pintype "passive"))
    )
    (net (code "39") (name "LED_R") (class "Default")
      (node (ref "R10") (pin "2") (pinfunction "2_2") (pintype "passive"))
      (node (ref "U1") (pin "39") (pinfunction "PB4B_39") (pintype "passive"))
    )
    (net (code "40") (name "MS2_CLOCK") (class "Default")
      (node (ref "PS/2") (pin "6") (pinfunction "6_6") (pintype "passive"))
      (node (ref "R24") (pin "2") (pinfunction "2_2") (pintype "passive"))
      (node (ref "U1") (pin "4") (pinfunction "PL4B_4") (pintype "passive"))
    )
    (net (code "41") (name "MS2_DATA") (class "Default")
      (node (ref "PS/2") (pin "2") (pinfunction "2_2") (pintype "passive"))
      (node (ref "R23") (pin "2") (pinfunction "2_2") (pintype "passive"))
      (node (ref "U1") (pin "5") (pinfunction "PL6A_5") (pintype "passive"))
    )
    (net (code "42") (name "Net-(C16-Pad2)") (class "Default")
      (node (ref "C16") (pin "2") (pinfunction "2_2") (pintype "passive"))
      (node (ref "R27") (pin "1") (pinfunction "1_1") (pintype "passive"))
      (node (ref "R28") (pin "1") (pinfunction "1_1") (pintype "passive"))
      (node (ref "R30") (pin "2") (pinfunction "2_2") (pintype "passive"))
    )
    (net (code "43") (name "Net-(C19-Pad1)") (class "Default")
      (node (ref "C19") (pin "1") (pinfunction "1_1") (pintype "passive"))
      (node (ref "R27") (pin "2") (pinfunction "2_2") (pintype "passive"))
      (node (ref "R29") (pin "1") (pinfunction "1_1") (pintype "passive"))
      (node (ref "R31") (pin "2") (pinfunction "2_2") (pintype "passive"))
    )
    (net (code "44") (name "Net-(C24-+)") (class "Default")
      (node (ref "C20") (pin "2") (pinfunction "2_2") (pintype "passive"))
      (node (ref "C24") (pin "A") (pinfunction "+_A") (pintype "passive"))
      (node (ref "R28") (pin "2") (pinfunction "2_2") (pintype "passive"))
    )
    (net (code "45") (name "Net-(C24--)") (class "Default")
      (node (ref "AUDIO") (pin "TIP") (pinfunction "TIP_TIP") (pintype "bidirectional"))
      (node (ref "C24") (pin "C") (pinfunction "-_C") (pintype "passive"))
    )
    (net (code "46") (name "Net-(C25-+)") (class "Default")
      (node (ref "C23") (pin "1") (pinfunction "1_1") (pintype "passive"))
      (node (ref "C25") (pin "A") (pinfunction "+_A") (pintype "passive"))
      (node (ref "R29") (pin "2") (pinfunction "2_2") (pintype "passive"))
    )
    (net (code "47") (name "Net-(C25--)") (class "Default")
      (node (ref "AUDIO") (pin "RING") (pinfunction "RING_RING") (pintype "bidirectional"))
      (node (ref "C25") (pin "C") (pinfunction "-_C") (pintype "passive"))
    )
    (net (code "48") (name "Net-(LED1-CBLUE)") (class "Default")
      (node (ref "LED1") (pin "P$1") (pinfunction "CBLUE_P$1") (pintype "passive"))
      (node (ref "R8") (pin "1") (pinfunction "1_1") (pintype "passive"))
    )
    (net (code "49") (name "Net-(LED1-CGREEN)") (class "Default")
      (node (ref "LED1") (pin "P$2") (pinfunction "CGREEN_P$2") (pintype "passive"))
      (node (ref "R9") (pin "1") (pinfunction "1_1") (pintype "passive"))
    )
    (net (code "50") (name "Net-(LED1-CRED)") (class "Default")
      (node (ref "LED1") (pin "P$4") (pinfunction "CRED_P$4") (pintype "passive"))
      (node (ref "R10") (pin "1") (pinfunction "1_1") (pintype "passive"))
    )
    (net (code "51") (name "Net-(LED2-PadA)") (class "Default")
      (node (ref "LED2") (pin "A") (pinfunction "A_A") (pintype "passive"))
      (node (ref "R47") (pin "2") (pinfunction "2_2") (pintype "passive"))
    )
    (net (code "52") (name "Net-(Q1-GND{slash}NC)") (class "Default")
      (node (ref "Q1") (pin "1") (pinfunction "GND/NC_1") (pintype "power_in"))
      (node (ref "R13") (pin "2") (pinfunction "2_2") (pintype "passive"))
    )
    (net (code "53") (name "Net-(Q1-OUT)") (class "Default")
      (node (ref "Q1") (pin "3") (pinfunction "OUT_3") (pintype "output"))
      (node (ref "R11") (pin "2") (pinfunction "2_2") (pintype "passive"))
    )
    (net (code "54") (name "Net-(R34-Pad2)") (class "Default")
      (node (ref "R34") (pin "2") (pinfunction "2_2") (pintype "passive"))
      (node (ref "R37") (pin "1") (pinfunction "1_1") (pintype "passive"))
      (node (ref "VIDEO") (pin "1") (pinfunction "1_1") (pintype "passive"))
    )
    (net (code "55") (name "Net-(R35-Pad2)") (class "Default")
      (node (ref "R35") (pin "2") (pinfunction "2_2") (pintype "passive"))
      (node (ref "R37") (pin "2") (pinfunction "2_2") (pintype "passive"))
      (node (ref "R38") (pin "1") (pinfunction "1_1") (pintype "passive"))
    )
    (net (code "56") (name "Net-(R36-Pad2)") (class "Default")
      (node (ref "R36") (pin "2") (pinfunction "2_2") (pintype "passive"))
      (node (ref "R38") (pin "2") (pinfunction "2_2") (pintype "passive"))
      (node (ref "R42") (pin "1") (pinfunction "1_1") (pintype "passive"))
    )
    (net (code "57") (name "Net-(R39-Pad2)") (class "Default")
      (node (ref "R39") (pin "2") (pinfunction "2_2") (pintype "passive"))
      (node (ref "R42") (pin "2") (pinfunction "2_2") (pintype "passive"))
      (node (ref "R43") (pin "1") (pinfunction "1_1") (pintype "passive"))
    )
    (net (code "58") (name "Net-(R40-Pad2)") (class "Default")
      (node (ref "R40") (pin "2") (pinfunction "2_2") (pintype "passive"))
      (node (ref "R43") (pin "2") (pinfunction "2_2") (pintype "passive"))
      (node (ref "R44") (pin "1") (pinfunction "1_1") (pintype "passive"))
    )
    (net (code "59") (name "Net-(R41-Pad2)") (class "Default")
      (node (ref "R41") (pin "2") (pinfunction "2_2") (pintype "passive"))
      (node (ref "R44") (pin "2") (pinfunction "2_2") (pintype "passive"))
      (node (ref "R45") (pin "1") (pinfunction "1_1") (pintype "passive"))
    )
    (net (code "60") (name "Net-(U$2-3V3OUT)") (class "Default")
      (node (ref "C13") (pin "1") (pinfunction "1_1") (pintype "passive"))
      (node (ref "U$2") (pin "6") (pinfunction "3V3OUT_6") (pintype "output"))
    )
    (net (code "61") (name "Net-(U$2-AVCC)") (class "Default")
      (node (ref "C14") (pin "1") (pinfunction "1_1") (pintype "passive"))
      (node (ref "R7") (pin "2") (pinfunction "2_2") (pintype "passive"))
      (node (ref "U$2") (pin "46") (pinfunction "AVCC_46") (pintype "bidirectional"))
    )
    (net (code "62") (name "Net-(U$2-EEDATA)") (class "Default")
      (node (ref "R46") (pin "2") (pinfunction "2_2") (pintype "passive"))
      (node (ref "U$2") (pin "2") (pinfunction "EEDATA_2") (pintype "bidirectional"))
    )
    (net (code "63") (name "Net-(U$2-RESET#)") (class "Default")
      (node (ref "R6") (pin "2") (pinfunction "2_2") (pintype "passive"))
      (node (ref "U$2") (pin "4") (pinfunction "RESET#_4") (pintype "bidirectional"))
    )
    (net (code "64") (name "Net-(U$2-RSTOUT#)") (class "Default")
      (node (ref "R5") (pin "1") (pinfunction "1_1") (pintype "passive"))
      (node (ref "U$2") (pin "5") (pinfunction "RSTOUT#_5") (pintype "bidirectional"))
    )
    (net (code "65") (name "Net-(U$2-USBDM)") (class "Default")
      (node (ref "R3") (pin "2") (pinfunction "2_2") (pintype "passive"))
      (node (ref "U$2") (pin "8") (pinfunction "USBDM_8") (pintype "bidirectional"))
    )
    (net (code "66") (name "Net-(U$2-USBDP)") (class "Default")
      (node (ref "R4") (pin "2") (pinfunction "2_2") (pintype "passive"))
      (node (ref "R5") (pin "2") (pinfunction "2_2") (pintype "passive"))
      (node (ref "U$2") (pin "7") (pinfunction "USBDP_7") (pintype "bidirectional"))
    )
    (net (code "67") (name "Net-(U$2-XTIN)") (class "Default")
      (node (ref "C17") (pin "1") (pinfunction "1_1") (pintype "passive"))
      (node (ref "R12") (pin "1") (pinfunction "1_1") (pintype "passive"))
      (node (ref "U$2") (pin "43") (pinfunction "XTIN_43") (pintype "bidirectional"))
      (node (ref "X1") (pin "1") (pinfunction "1_1") (pintype "passive"))
    )
    (net (code "68") (name "Net-(U$2-XTOUT)") (class "Default")
      (node (ref "C18") (pin "1") (pinfunction "1_1") (pintype "passive"))
      (node (ref "R12") (pin "2") (pinfunction "2_2") (pintype "passive"))
      (node (ref "U$2") (pin "44") (pinfunction "XTOUT_44") (pintype "bidirectional"))
      (node (ref "X1") (pin "2") (pinfunction "2_2") (pintype "passive"))
    )
    (net (code "69") (name "Net-(U2-D+)") (class "Default")
      (node (ref "R4") (pin "1") (pinfunction "1_1") (pintype "passive"))
      (node (ref "U2") (pin "D+1") (pinfunction "D+_D+1") (pintype "bidirectional"))
    )
    (net (code "70") (name "Net-(U2-D-)") (class "Default")
      (node (ref "R3") (pin "1") (pinfunction "1_1") (pintype "passive"))
      (node (ref "U2") (pin "D-1") (pinfunction "D-_D-1") (pintype "bidirectional"))
    )
    (net (code "71") (name "PROGRAMN") (class "Default")
      (node (ref "R21") (pin "1") (pinfunction "1_1") (pintype "passive"))
      (node (ref "U1") (pin "119") (pinfunction "PT27D_119") (pintype "passive"))
    )
    (net (code "72") (name "PS2_CLOCK") (class "Default")
      (node (ref "PS/2") (pin "5") (pinfunction "5_5") (pintype "passive"))
      (node (ref "R25") (pin "2") (pinfunction "2_2") (pintype "passive"))
      (node (ref "U1") (pin "2") (pinfunction "PL3B_2") (pintype "passive"))
    )
    (net (code "73") (name "PS2_DATA") (class "Default")
      (node (ref "PS/2") (pin "1") (pinfunction "1_1") (pintype "passive"))
      (node (ref "R26") (pin "2") (pinfunction "2_2") (pintype "passive"))
      (node (ref "U1") (pin "138") (pinfunction "PT11B_138") (pintype "passive"))
    )
    (net (code "74") (name "SCL") (class "Default")
      (node (ref "JP4") (pin "2") (pinfunction "2_2") (pintype "passive"))
      (node (ref "R1") (pin "1") (pinfunction "1_1") (pintype "passive"))
      (node (ref "U1") (pin "126") (pinfunction "PT22C_126") (pintype "passive"))
    )
    (net (code "75") (name "SDA") (class "Default")
      (node (ref "JP4") (pin "3") (pinfunction "3_3") (pintype "passive"))
      (node (ref "R2") (pin "1") (pinfunction "1_1") (pintype "passive"))
      (node (ref "U1") (pin "125") (pinfunction "PT22D_125") (pintype "passive"))
    )
    (net (code "76") (name "SEG_A1") (class "Default")
      (node (ref "U$3") (pin "17") (pinfunction "A1_17") (pintype "bidirectional"))
      (node (ref "U1") (pin "115") (pinfunction "PT28B_115") (pintype "passive"))
    )
    (net (code "77") (name "SEG_A2") (class "Default")
      (node (ref "U$3") (pin "12") (pinfunction "A2_12") (pintype "bidirectional"))
      (node (ref "U1") (pin "127") (pinfunction "PT18B_127") (pintype "passive"))
    )
    (net (code "78") (name "SEG_B1") (class "Default")
      (node (ref "U$3") (pin "16") (pinfunction "B1_16") (pintype "bidirectional"))
      (node (ref "U1") (pin "117") (pinfunction "PT28A_117") (pintype "passive"))
    )
    (net (code "79") (name "SEG_B2") (class "Default")
      (node (ref "U$3") (pin "11") (pinfunction "B2_11") (pintype "bidirectional"))
      (node (ref "U1") (pin "128") (pinfunction "PT18A_128") (pintype "passive"))
    )
    (net (code "80") (name "SEG_C1") (class "Default")
      (node (ref "U$3") (pin "4") (pinfunction "C1_4") (pintype "bidirectional"))
      (node (ref "U1") (pin "103") (pinfunction "PR4C_103") (pintype "passive"))
    )
    (net (code "81") (name "SEG_C2") (class "Default")
      (node (ref "U$3") (pin "9") (pinfunction "C2_9") (pintype "bidirectional"))
      (node (ref "U1") (pin "111") (pinfunction "PT35B_111") (pintype "passive"))
    )
    (net (code "82") (name "SEG_D1") (class "Default")
      (node (ref "U$3") (pin "2") (pinfunction "D1_2") (pintype "bidirectional"))
      (node (ref "U1") (pin "99") (pinfunction "PR5B_99") (pintype "passive"))
    )
    (net (code "83") (name "SEG_D2") (class "Default")
      (node (ref "U$3") (pin "7") (pinfunction "D2_7") (pintype "bidirectional"))
      (node (ref "U1") (pin "106") (pinfunction "PR2B_106") (pintype "passive"))
    )
    (net (code "84") (name "SEG_DIG1") (class "Default")
      (node (ref "U$3") (pin "18") (pinfunction "DIG2_18") (pintype "bidirectional"))
      (node (ref "U$3") (pin "3") (pinfunction "DIG1_3") (pintype "bidirectional"))
      (node (ref "U1") (pin "100") (pinfunction "PR5A_100") (pintype "passive"))
    )
    (net (code "85") (name "SEG_DIG2") (class "Default")
      (node (ref "U$3") (pin "13") (pinfunction "DIG4_13") (pintype "bidirectional"))
      (node (ref "U$3") (pin "8") (pinfunction "DIG3_8") (pintype "bidirectional"))
      (node (ref "U1") (pin "107") (pinfunction "PR2A_107") (pintype "passive"))
    )
    (net (code "86") (name "SEG_DP1") (class "Default")
      (node (ref "U$3") (pin "5") (pinfunction "DP1_5") (pintype "bidirectional"))
      (node (ref "U1") (pin "104") (pinfunction "PR3B_104") (pintype "passive"))
    )
    (net (code "87") (name "SEG_DP2") (class "Default")
      (node (ref "U$3") (pin "10") (pinfunction "DP2_10") (pintype "bidirectional"))
      (node (ref "U1") (pin "112") (pinfunction "PT35A_112") (pintype "passive"))
    )
    (net (code "88") (name "SEG_E1") (class "Default")
      (node (ref "U$3") (pin "1") (pinfunction "E1_1") (pintype "bidirectional"))
      (node (ref "U1") (pin "98") (pinfunction "PR7A_98") (pintype "passive"))
    )
    (net (code "89") (name "SEG_E2") (class "Default")
      (node (ref "U$3") (pin "6") (pinfunction "E2_6") (pintype "bidirectional"))
      (node (ref "U1") (pin "105") (pinfunction "PR3A_105") (pintype "passive"))
    )
    (net (code "90") (name "SEG_F1") (class "Default")
      (node (ref "U$3") (pin "19") (pinfunction "F1_19") (pintype "bidirectional"))
      (node (ref "U1") (pin "114") (pinfunction "PT33A_114") (pintype "passive"))
    )
    (net (code "91") (name "SEG_F2") (class "Default")
      (node (ref "U$3") (pin "14") (pinfunction "F2_14") (pintype "bidirectional"))
      (node (ref "U1") (pin "122") (pinfunction "PT25A_122") (pintype "passive"))
    )
    (net (code "92") (name "SEG_G1") (class "Default")
      (node (ref "U$3") (pin "20") (pinfunction "G1_20") (pintype "bidirectional"))
      (node (ref "U1") (pin "113") (pinfunction "PT33B_113") (pintype "passive"))
    )
    (net (code "93") (name "SEG_G2") (class "Default")
      (node (ref "U$3") (pin "15") (pinfunction "G2_15") (pintype "bidirectional"))
      (node (ref "U1") (pin "121") (pinfunction "PT25B_121") (pintype "passive"))
    )
    (net (code "94") (name "SN") (class "Default")
      (node (ref "R20") (pin "1") (pinfunction "1_1") (pintype "passive"))
      (node (ref "U1") (pin "70") (pinfunction "PB38A_70") (pintype "passive"))
    )
    (net (code "95") (name "SPI_CLK") (class "Default")
      (node (ref "U$1") (pin "5") (pinfunction "SCK,PIN5_5") (pintype "bidirectional"))
      (node (ref "U1") (pin "44") (pinfunction "PB12A_44") (pintype "passive"))
    )
    (net (code "96") (name "SPI_CS") (class "Default")
      (node (ref "U$1") (pin "1") (pinfunction "CS,PIN1_1") (pintype "bidirectional"))
      (node (ref "U1") (pin "40") (pinfunction "PB6A_40") (pintype "passive"))
    )
    (net (code "97") (name "SPI_MISO") (class "Default")
      (node (ref "U$1") (pin "7") (pinfunction "DO,PIN7_7") (pintype "bidirectional"))
      (node (ref "U1") (pin "45") (pinfunction "PB12B_45") (pintype "passive"))
    )
    (net (code "98") (name "SPI_MOSI") (class "Default")
      (node (ref "U$1") (pin "2") (pinfunction "DI,PIN2_2") (pintype "bidirectional"))
      (node (ref "U1") (pin "71") (pinfunction "PB38B_71") (pintype "passive"))
    )
    (net (code "99") (name "SRAM_A0") (class "Default")
      (node (ref "IC1") (pin "5") (pinfunction "A0_5") (pintype "input"))
      (node (ref "U1") (pin "50") (pinfunction "PB16B_50") (pintype "passive"))
    )
    (net (code "100") (name "SRAM_A1") (class "Default")
      (node (ref "IC1") (pin "4") (pinfunction "A1_4") (pintype "input"))
      (node (ref "U1") (pin "49") (pinfunction "PB16A_49") (pintype "passive"))
    )
    (net (code "101") (name "SRAM_A2") (class "Default")
      (node (ref "IC1") (pin "3") (pinfunction "A2_3") (pintype "input"))
      (node (ref "U1") (pin "48") (pinfunction "PB13B_48") (pintype "passive"))
    )
    (net (code "102") (name "SRAM_A3") (class "Default")
      (node (ref "IC1") (pin "2") (pinfunction "A3_2") (pintype "input"))
      (node (ref "U1") (pin "47") (pinfunction "PB13A_47") (pintype "passive"))
    )
    (net (code "103") (name "SRAM_A4") (class "Default")
      (node (ref "IC1") (pin "1") (pinfunction "A4_1") (pintype "input"))
      (node (ref "U1") (pin "43") (pinfunction "PB9B_43") (pintype "passive"))
    )
    (net (code "104") (name "SRAM_A5") (class "Default")
      (node (ref "IC1") (pin "48") (pinfunction "A5_48") (pintype "input"))
      (node (ref "U1") (pin "73") (pinfunction "PR24B_73") (pintype "passive"))
    )
    (net (code "105") (name "SRAM_A6") (class "Default")
      (node (ref "IC1") (pin "47") (pinfunction "A6_47") (pintype "input"))
      (node (ref "U1") (pin "74") (pinfunction "PR24A_74") (pintype "passive"))
    )
    (net (code "106") (name "SRAM_A7") (class "Default")
      (node (ref "IC1") (pin "46") (pinfunction "A7_46") (pintype "input"))
      (node (ref "U1") (pin "75") (pinfunction "PR23B_75") (pintype "passive"))
    )
    (net (code "107") (name "SRAM_A8") (class "Default")
      (node (ref "IC1") (pin "45") (pinfunction "A8_45") (pintype "input"))
      (node (ref "U1") (pin "76") (pinfunction "PR23A_76") (pintype "passive"))
    )
    (net (code "108") (name "SRAM_A9") (class "Default")
      (node (ref "IC1") (pin "30") (pinfunction "A9_30") (pintype "input"))
      (node (ref "U1") (pin "92") (pinfunction "PR12A_92") (pintype "passive"))
    )
    (net (code "109") (name "SRAM_A10") (class "Default")
      (node (ref "IC1") (pin "29") (pinfunction "A10_29") (pintype "input"))
      (node (ref "U1") (pin "93") (pinfunction "PR11B_93") (pintype "passive"))
    )
    (net (code "110") (name "SRAM_A11") (class "Default")
      (node (ref "IC1") (pin "28") (pinfunction "A11_28") (pintype "input"))
      (node (ref "U1") (pin "94") (pinfunction "PR11A_94") (pintype "passive"))
    )
    (net (code "111") (name "SRAM_A12") (class "Default")
      (node (ref "IC1") (pin "27") (pinfunction "A12_27") (pintype "input"))
      (node (ref "U1") (pin "95") (pinfunction "PR9B_95") (pintype "passive"))
    )
    (net (code "112") (name "SRAM_A13") (class "Default")
      (node (ref "IC1") (pin "26") (pinfunction "A13_26") (pintype "input"))
      (node (ref "U1") (pin "96") (pinfunction "PR9A_96") (pintype "passive"))
    )
    (net (code "113") (name "SRAM_A14") (class "Default")
      (node (ref "IC1") (pin "25") (pinfunction "A14_25") (pintype "input"))
      (node (ref "U1") (pin "97") (pinfunction "PR7B_97") (pintype "passive"))
    )
    (net (code "114") (name "SRAM_A15") (class "Default")
      (node (ref "IC1") (pin "24") (pinfunction "A15_24") (pintype "input"))
      (node (ref "U1") (pin "69") (pinfunction "PB37B_69") (pintype "passive"))
    )
    (net (code "115") (name "SRAM_A16") (class "Default")
      (node (ref "IC1") (pin "23") (pinfunction "A16_23") (pintype "input"))
      (node (ref "U1") (pin "68") (pinfunction "PB37A_68") (pintype "passive"))
    )
    (net (code "116") (name "SRAM_A17") (class "Default")
      (node (ref "IC1") (pin "22") (pinfunction "A17_22") (pintype "input"))
      (node (ref "U1") (pin "67") (pinfunction "PB35B_67") (pintype "passive"))
    )
    (net (code "117") (name "SRAM_A18") (class "Default")
      (node (ref "IC1") (pin "21") (pinfunction "A18_21") (pintype "input"))
      (node (ref "U1") (pin "65") (pinfunction "PB35A_65") (pintype "passive"))
    )
    (net (code "118") (name "SRAM_A19") (class "Default")
      (node (ref "IC1") (pin "20") (pinfunction "A19_20") (pintype "input"))
      (node (ref "U1") (pin "63") (pinfunction "PB31D_63") (pintype "passive"))
    )
    (net (code "119") (name "SRAM_CE") (class "Default")
      (node (ref "IC1") (pin "7") (pinfunction "~{CE}_7") (pintype "input"))
      (node (ref "U1") (pin "52") (pinfunction "PB18A_52") (pintype "passive"))
    )
    (net (code "120") (name "SRAM_D0") (class "Default")
      (node (ref "IC1") (pin "8") (pinfunction "I/O0_8") (pintype "tri_state"))
      (node (ref "U1") (pin "54") (pinfunction "PB18B_54") (pintype "passive"))
    )
    (net (code "121") (name "SRAM_D1") (class "Default")
      (node (ref "IC1") (pin "9") (pinfunction "I/O1_9") (pintype "tri_state"))
      (node (ref "U1") (pin "55") (pinfunction "PB23A_55") (pintype "passive"))
    )
    (net (code "122") (name "SRAM_D2") (class "Default")
      (node (ref "IC1") (pin "10") (pinfunction "I/O2_10") (pintype "tri_state"))
      (node (ref "U1") (pin "56") (pinfunction "PB23B_56") (pintype "passive"))
    )
    (net (code "123") (name "SRAM_D3") (class "Default")
      (node (ref "IC1") (pin "11") (pinfunction "I/O3_11") (pintype "tri_state"))
      (node (ref "U1") (pin "57") (pinfunction "PB26A_57") (pintype "passive"))
    )
    (net (code "124") (name "SRAM_D4") (class "Default")
      (node (ref "IC1") (pin "14") (pinfunction "I/O4_14") (pintype "tri_state"))
      (node (ref "U1") (pin "58") (pinfunction "PB26B_58") (pintype "passive"))
    )
    (net (code "125") (name "SRAM_D5") (class "Default")
      (node (ref "IC1") (pin "15") (pinfunction "I/O5_15") (pintype "tri_state"))
      (node (ref "U1") (pin "59") (pinfunction "PB29A_59") (pintype "passive"))
    )
    (net (code "126") (name "SRAM_D6") (class "Default")
      (node (ref "IC1") (pin "16") (pinfunction "I/O6_16") (pintype "tri_state"))
      (node (ref "U1") (pin "60") (pinfunction "PB29B_60") (pintype "passive"))
    )
    (net (code "127") (name "SRAM_D7") (class "Default")
      (node (ref "IC1") (pin "17") (pinfunction "I/O7_17") (pintype "tri_state"))
      (node (ref "U1") (pin "61") (pinfunction "PB31A_61") (pintype "passive"))
    )
    (net (code "128") (name "SRAM_D8") (class "Default")
      (node (ref "IC1") (pin "32") (pinfunction "I/O8_32") (pintype "tri_state"))
      (node (ref "U1") (pin "91") (pinfunction "PR12B_91") (pintype "passive"))
    )
    (net (code "129") (name "SRAM_D9") (class "Default")
      (node (ref "IC1") (pin "33") (pinfunction "I/O9_33") (pintype "tri_state"))
      (node (ref "U1") (pin "89") (pinfunction "PR15A_89") (pintype "passive"))
    )
    (net (code "130") (name "SRAM_D10") (class "Default")
      (node (ref "IC1") (pin "34") (pinfunction "I/O10_34") (pintype "tri_state"))
      (node (ref "U1") (pin "87") (pinfunction "PR15B_87") (pintype "passive"))
    )
    (net (code "131") (name "SRAM_D11") (class "Default")
      (node (ref "IC1") (pin "35") (pinfunction "I/O11_35") (pintype "tri_state"))
      (node (ref "U1") (pin "86") (pinfunction "PR16A_86") (pintype "passive"))
    )
    (net (code "132") (name "SRAM_D12") (class "Default")
      (node (ref "IC1") (pin "38") (pinfunction "I/O12_38") (pintype "tri_state"))
      (node (ref "U1") (pin "85") (pinfunction "PR16B_85") (pintype "passive"))
    )
    (net (code "133") (name "SRAM_D13") (class "Default")
      (node (ref "IC1") (pin "39") (pinfunction "I/O13_39") (pintype "tri_state"))
      (node (ref "U1") (pin "84") (pinfunction "PR17A_84") (pintype "passive"))
    )
    (net (code "134") (name "SRAM_D14") (class "Default")
      (node (ref "IC1") (pin "40") (pinfunction "I/O14_40") (pintype "tri_state"))
      (node (ref "U1") (pin "83") (pinfunction "PR17B_83") (pintype "passive"))
    )
    (net (code "135") (name "SRAM_D15") (class "Default")
      (node (ref "IC1") (pin "41") (pinfunction "I/O15_41") (pintype "tri_state"))
      (node (ref "U1") (pin "82") (pinfunction "PR18A_82") (pintype "passive"))
    )
    (net (code "136") (name "SRAM_LB") (class "Default")
      (node (ref "IC1") (pin "42") (pinfunction "~{LB}_42") (pintype "input"))
      (node (ref "U1") (pin "81") (pinfunction "PR18B_81") (pintype "passive"))
    )
    (net (code "137") (name "SRAM_OE") (class "Default")
      (node (ref "IC1") (pin "44") (pinfunction "~{OE}_44") (pintype "input"))
      (node (ref "U1") (pin "77") (pinfunction "PR21B_77") (pintype "passive"))
    )
    (net (code "138") (name "SRAM_UB") (class "Default")
      (node (ref "IC1") (pin "43") (pinfunction "~{UB}_43") (pintype "input"))
      (node (ref "U1") (pin "78") (pinfunction "PR21A_78") (pintype "passive"))
    )
    (net (code "139") (name "SRAM_WE") (class "Default")
      (node (ref "IC1") (pin "18") (pinfunction "~{WE}_18") (pintype "input"))
      (node (ref "U1") (pin "62") (pinfunction "PB31B_62") (pintype "passive"))
    )
    (net (code "140") (name "USBAURT_TX") (class "Default")
      (node (ref "U$2") (pin "40") (pinfunction "BDBUS0_40") (pintype "output"))
      (node (ref "U1") (pin "133") (pinfunction "PT15A_133") (pintype "passive"))
    )
    (net (code "141") (name "USBJTAG_TCK") (class "Default")
      (node (ref "JP1") (pin "8") (pinfunction "8_8") (pintype "passive"))
      (node (ref "R14") (pin "2") (pinfunction "2_2") (pintype "passive"))
      (node (ref "U$2") (pin "24") (pinfunction "ADBUS0_24") (pintype "bidirectional"))
    )
    (net (code "142") (name "USBJTAG_TDI") (class "Default")
      (node (ref "JP1") (pin "6") (pinfunction "6_6") (pintype "passive"))
      (node (ref "R15") (pin "1") (pinfunction "1_1") (pintype "passive"))
      (node (ref "U$2") (pin "23") (pinfunction "ADBUS1_23") (pintype "bidirectional"))
    )
    (net (code "143") (name "USBJTAG_TDO") (class "Default")
      (node (ref "JP1") (pin "4") (pinfunction "4_4") (pintype "passive"))
      (node (ref "R16") (pin "1") (pinfunction "1_1") (pintype "passive"))
      (node (ref "U$2") (pin "22") (pinfunction "ADBUS2_22") (pintype "bidirectional"))
    )
    (net (code "144") (name "USBJTAG_TMS") (class "Default")
      (node (ref "JP1") (pin "10") (pinfunction "10_10") (pintype "passive"))
      (node (ref "R17") (pin "1") (pinfunction "1_1") (pintype "passive"))
      (node (ref "U$2") (pin "21") (pinfunction "ADBUS3_21") (pintype "bidirectional"))
    )
    (net (code "145") (name "USBUART_RX") (class "Default")
      (node (ref "U$2") (pin "39") (pinfunction "BDBUS1_39") (pintype "input"))
      (node (ref "U1") (pin "132") (pinfunction "PT15B_132") (pintype "passive"))
    )
    (net (code "146") (name "VID0") (class "Default")
      (node (ref "R41") (pin "1") (pinfunction "1_1") (pintype "passive"))
      (node (ref "U1") (pin "142") (pinfunction "PT9B_142") (pintype "passive"))
    )
    (net (code "147") (name "VID1") (class "Default")
      (node (ref "R40") (pin "1") (pinfunction "1_1") (pintype "passive"))
      (node (ref "U1") (pin "143") (pinfunction "PT9A_143") (pintype "passive"))
    )
    (net (code "148") (name "VID2") (class "Default")
      (node (ref "R39") (pin "1") (pinfunction "1_1") (pintype "passive"))
      (node (ref "U1") (pin "1") (pinfunction "PL3A_1") (pintype "passive"))
    )
    (net (code "149") (name "VID3") (class "Default")
      (node (ref "R36") (pin "1") (pinfunction "1_1") (pintype "passive"))
      (node (ref "U1") (pin "141") (pinfunction "PT10A_141") (pintype "passive"))
    )
    (net (code "150") (name "VID4") (class "Default")
      (node (ref "R35") (pin "1") (pinfunction "1_1") (pintype "passive"))
      (node (ref "U1") (pin "140") (pinfunction "PT10B_140") (pintype "passive"))
    )
    (net (code "151") (name "VID5") (class "Default")
      (node (ref "R34") (pin "1") (pinfunction "1_1") (pintype "passive"))
      (node (ref "U1") (pin "139") (pinfunction "PT11A_139") (pintype "passive"))
    )
    (net (code "152") (name "unconnected-(AUDIO-PadRSH)") (class "Default")
      (node (ref "AUDIO") (pin "RSH") (pinfunction "RSH_RSH") (pintype "bidirectional"))
    )
    (net (code "153") (name "unconnected-(AUDIO-PadTSH)") (class "Default")
      (node (ref "AUDIO") (pin "TSH") (pinfunction "TSH_TSH") (pintype "bidirectional"))
    )
    (net (code "154") (name "unconnected-(U$1-IR1Q,PIN8-Pad8)") (class "Default")
      (node (ref "U$1") (pin "8") (pinfunction "IR1Q,PIN8_8") (pintype "bidirectional"))
    )
    (net (code "155") (name "unconnected-(U$1-PIN9-Pad9)") (class "Default")
      (node (ref "U$1") (pin "9") (pinfunction "PIN9_9") (pintype "bidirectional"))
    )
    (net (code "156") (name "unconnected-(U$1-PadCD)") (class "Default")
      (node (ref "U$1") (pin "CD") (pinfunction "CD_CD") (pintype "bidirectional"))
    )
    (net (code "157") (name "unconnected-(U$1-PadWP)") (class "Default")
      (node (ref "U$1") (pin "WP") (pinfunction "WP_WP") (pintype "bidirectional"))
    )
    (net (code "158") (name "unconnected-(U$2-ACBUS0-Pad15)") (class "Default")
      (node (ref "U$2") (pin "15") (pinfunction "ACBUS0_15") (pintype "bidirectional"))
    )
    (net (code "159") (name "unconnected-(U$2-ACBUS1-Pad13)") (class "Default")
      (node (ref "U$2") (pin "13") (pinfunction "ACBUS1_13") (pintype "bidirectional"))
    )
    (net (code "160") (name "unconnected-(U$2-ACBUS2-Pad12)") (class "Default")
      (node (ref "U$2") (pin "12") (pinfunction "ACBUS2_12") (pintype "bidirectional"))
    )
    (net (code "161") (name "unconnected-(U$2-ACBUS3-Pad11)") (class "Default")
      (node (ref "U$2") (pin "11") (pinfunction "ACBUS3_11") (pintype "bidirectional"))
    )
    (net (code "162") (name "unconnected-(U$2-ADBUS4-Pad20)") (class "Default")
      (node (ref "U$2") (pin "20") (pinfunction "ADBUS4_20") (pintype "bidirectional"))
    )
    (net (code "163") (name "unconnected-(U$2-ADBUS5-Pad19)") (class "Default")
      (node (ref "U$2") (pin "19") (pinfunction "ADBUS5_19") (pintype "bidirectional"))
    )
    (net (code "164") (name "unconnected-(U$2-ADBUS6-Pad17)") (class "Default")
      (node (ref "U$2") (pin "17") (pinfunction "ADBUS6_17") (pintype "bidirectional"))
    )
    (net (code "165") (name "unconnected-(U$2-ADBUS7-Pad16)") (class "Default")
      (node (ref "U$2") (pin "16") (pinfunction "ADBUS7_16") (pintype "bidirectional"))
    )
    (net (code "166") (name "unconnected-(U$2-BCBUS0-Pad30)") (class "Default")
      (node (ref "U$2") (pin "30") (pinfunction "BCBUS0_30") (pintype "bidirectional"))
    )
    (net (code "167") (name "unconnected-(U$2-BCBUS1-Pad29)") (class "Default")
      (node (ref "U$2") (pin "29") (pinfunction "BCBUS1_29") (pintype "bidirectional"))
    )
    (net (code "168") (name "unconnected-(U$2-BCBUS2-Pad28)") (class "Default")
      (node (ref "U$2") (pin "28") (pinfunction "BCBUS2_28") (pintype "bidirectional"))
    )
    (net (code "169") (name "unconnected-(U$2-BCBUS3-Pad27)") (class "Default")
      (node (ref "U$2") (pin "27") (pinfunction "BCBUS3_27") (pintype "bidirectional"))
    )
    (net (code "170") (name "unconnected-(U$2-BDBUS2-Pad38)") (class "Default")
      (node (ref "U$2") (pin "38") (pinfunction "BDBUS2_38") (pintype "output"))
    )
    (net (code "171") (name "unconnected-(U$2-BDBUS3-Pad37)") (class "Default")
      (node (ref "U$2") (pin "37") (pinfunction "BDBUS3_37") (pintype "input"))
    )
    (net (code "172") (name "unconnected-(U$2-BDBUS4-Pad36)") (class "Default")
      (node (ref "U$2") (pin "36") (pinfunction "BDBUS4_36") (pintype "output"))
    )
    (net (code "173") (name "unconnected-(U$2-BDBUS5-Pad35)") (class "Default")
      (node (ref "U$2") (pin "35") (pinfunction "BDBUS5_35") (pintype "input"))
    )
    (net (code "174") (name "unconnected-(U$2-BDBUS6-Pad33)") (class "Default")
      (node (ref "U$2") (pin "33") (pinfunction "BDBUS6_33") (pintype "input"))
    )
    (net (code "175") (name "unconnected-(U$2-BDBUS7-Pad32)") (class "Default")
      (node (ref "U$2") (pin "32") (pinfunction "BDBUS7_32") (pintype "input"))
    )
    (net (code "176") (name "unconnected-(U$2-EECS-Pad48)") (class "Default")
      (node (ref "U$2") (pin "48") (pinfunction "EECS_48") (pintype "bidirectional"))
    )
    (net (code "177") (name "unconnected-(U$2-EESK-Pad1)") (class "Default")
      (node (ref "U$2") (pin "1") (pinfunction "EESK_1") (pintype "bidirectional"))
    )
    (net (code "178") (name "unconnected-(U$2-PWEN#-Pad41)") (class "Default")
      (node (ref "U$2") (pin "41") (pinfunction "PWEN#_41") (pintype "bidirectional"))
    )
    (net (code "179") (name "unconnected-(U$2-SI{slash}WUA-Pad10)") (class "Default")
      (node (ref "U$2") (pin "10") (pinfunction "SI/WUA_10") (pintype "bidirectional"))
    )
    (net (code "180") (name "unconnected-(U$2-SI{slash}WUB-Pad26)") (class "Default")
      (node (ref "U$2") (pin "26") (pinfunction "SI/WUB_26") (pintype "bidirectional"))
    )
    (net (code "181") (name "unconnected-(U1B-NC-Pad129)") (class "Default")
      (node (ref "U1") (pin "129") (pinfunction "NC_129") (pintype "no_connect"))
    )
    (net (code "182") (name "unconnected-(U2-USBID-PadID1)") (class "Default")
      (node (ref "U2") (pin "ID1") (pinfunction "USBID_ID1") (pintype "bidirectional"))
    )
  )
)
